# 04_-_ZYNQ_POWER_AND_JTAG.net
KiCad netlist of a schematic drawn in Altium Designer
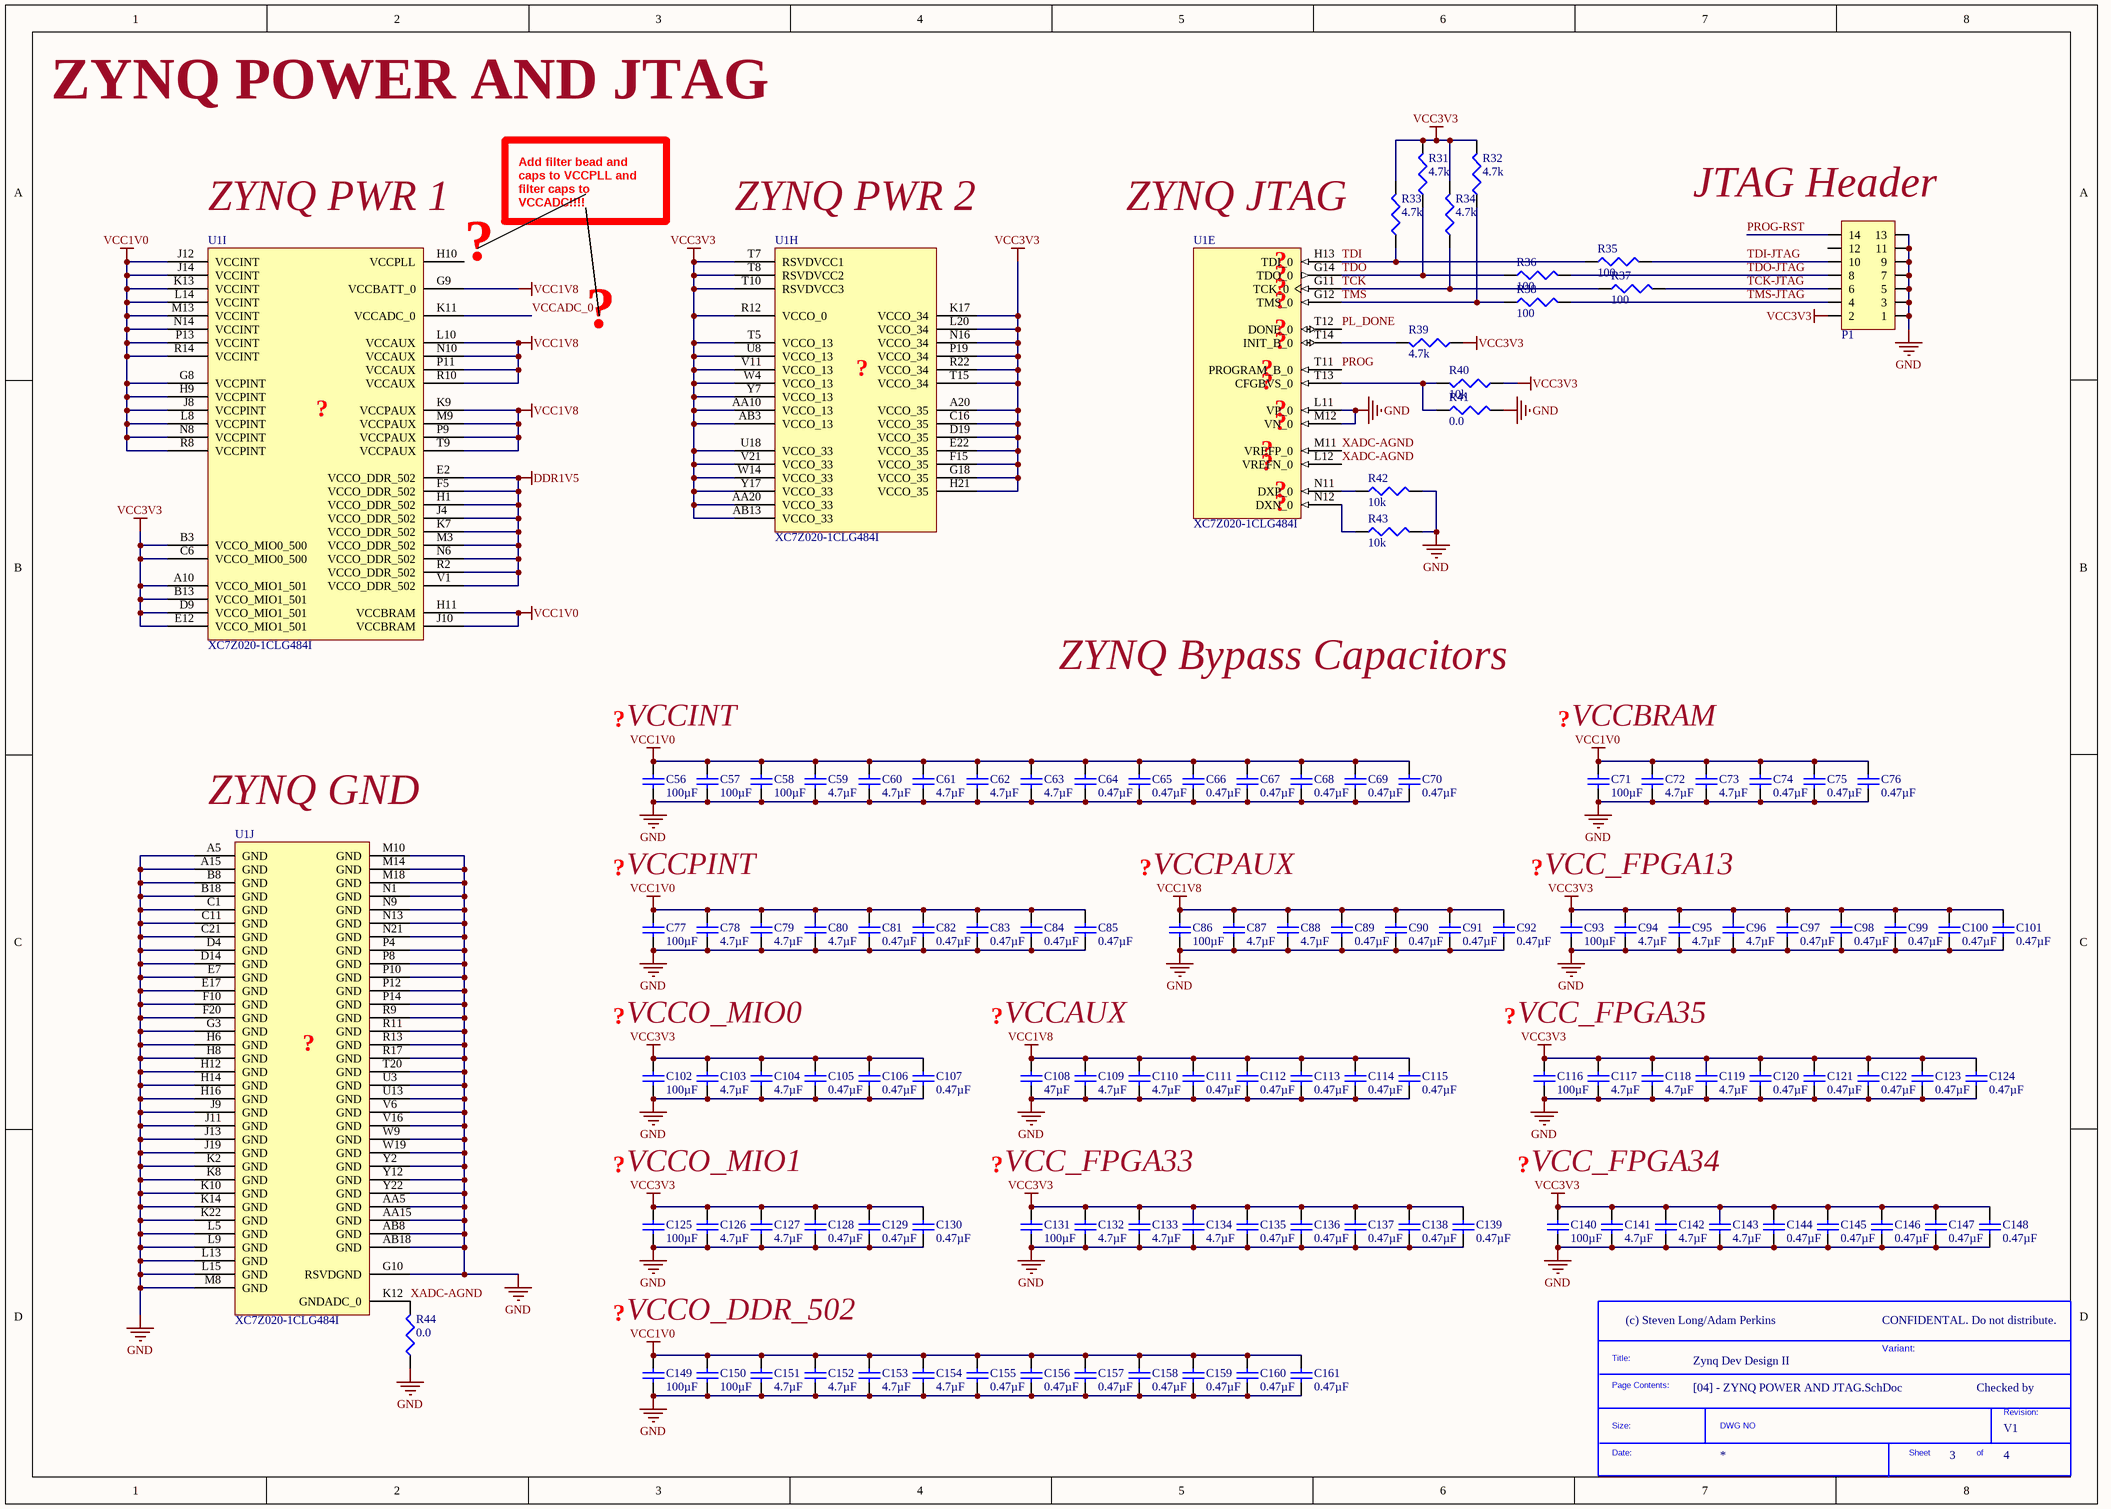
[diagram p0: [04] - ZYNQ POWER AND JTAG.SchDoc]

(export (version "E")
  (design (tool "Eeschema 10.0.6"))
  (components
    (comp (ref "C56")
      (value "GRM32EE70G107ME19L")
      (footprint "CAP-1210")
      (description "CAP CER 100UF 4V X7U 1210")
      (fields
        (field (name "MANUFACTURER") "Murata Electronics North America")
        (field (name "TOLERANCE") "±20%")
        (field (name "CAPACITANCE") "100µF")
      )
      (libsource (lib "zynq_dev_V1") (part "GRM32EE70G107ME19L"))
    )
    (comp (ref "C57")
      (value "GRM32EE70G107ME19L")
      (footprint "CAP-1210")
      (description "CAP CER 100UF 4V X7U 1210")
      (fields
        (field (name "MANUFACTURER") "Murata Electronics North America")
        (field (name "TOLERANCE") "±20%")
        (field (name "CAPACITANCE") "100µF")
      )
      (libsource (lib "zynq_dev_V1") (part "GRM32EE70G107ME19L"))
    )
    (comp (ref "C58")
      (value "GRM32EE70G107ME19L")
      (footprint "CAP-1210")
      (description "CAP CER 100UF 4V X7U 1210")
      (fields
        (field (name "MANUFACTURER") "Murata Electronics North America")
        (field (name "TOLERANCE") "±20%")
        (field (name "CAPACITANCE") "100µF")
      )
      (libsource (lib "zynq_dev_V1") (part "GRM32EE70G107ME19L"))
    )
    (comp (ref "C59")
      (value "GRM188R60J475KE19D")
      (footprint "CAP-0603")
      (description "CAP CER 4.7UF 6.3V X5R 0603")
      (fields
        (field (name "MANUFACTURER") "Murata Electronics North America")
        (field (name "TOLERANCE") "±10%")
        (field (name "CAPACITANCE") "4.7µF")
      )
      (libsource (lib "zynq_dev_V1") (part "GRM188R60J475KE19D"))
    )
    (comp (ref "C60")
      (value "GRM188R60J475KE19D")
      (footprint "CAP-0603")
      (description "CAP CER 4.7UF 6.3V X5R 0603")
      (fields
        (field (name "MANUFACTURER") "Murata Electronics North America")
        (field (name "TOLERANCE") "±10%")
        (field (name "CAPACITANCE") "4.7µF")
      )
      (libsource (lib "zynq_dev_V1") (part "GRM188R60J475KE19D"))
    )
    (comp (ref "C61")
      (value "GRM188R60J475KE19D")
      (footprint "CAP-0603")
      (description "CAP CER 4.7UF 6.3V X5R 0603")
      (fields
        (field (name "MANUFACTURER") "Murata Electronics North America")
        (field (name "TOLERANCE") "±10%")
        (field (name "CAPACITANCE") "4.7µF")
      )
      (libsource (lib "zynq_dev_V1") (part "GRM188R60J475KE19D"))
    )
    (comp (ref "C62")
      (value "GRM188R60J475KE19D")
      (footprint "CAP-0603")
      (description "CAP CER 4.7UF 6.3V X5R 0603")
      (fields
        (field (name "MANUFACTURER") "Murata Electronics North America")
        (field (name "TOLERANCE") "±10%")
        (field (name "CAPACITANCE") "4.7µF")
      )
      (libsource (lib "zynq_dev_V1") (part "GRM188R60J475KE19D"))
    )
    (comp (ref "C63")
      (value "GRM188R60J475KE19D")
      (footprint "CAP-0603")
      (description "CAP CER 4.7UF 6.3V X5R 0603")
      (fields
        (field (name "MANUFACTURER") "Murata Electronics North America")
        (field (name "TOLERANCE") "±10%")
        (field (name "CAPACITANCE") "4.7µF")
      )
      (libsource (lib "zynq_dev_V1") (part "GRM188R60J475KE19D"))
    )
    (comp (ref "C64")
      (value "C1005X7S1A474K050BC")
      (footprint "CAP-0402")
      (description "CAP CER 0.47UF 10V X7S 0402")
      (fields
        (field (name "MANUFACTURER") "TDK Corporation")
        (field (name "TOLERANCE") "±10%")
        (field (name "CAPACITANCE") "0.47µF")
      )
      (libsource (lib "zynq_dev_V1") (part "C1005X7S1A474K050BC"))
    )
    (comp (ref "C65")
      (value "C1005X7S1A474K050BC")
      (footprint "CAP-0402")
      (description "CAP CER 0.47UF 10V X7S 0402")
      (fields
        (field (name "MANUFACTURER") "TDK Corporation")
        (field (name "TOLERANCE") "±10%")
        (field (name "CAPACITANCE") "0.47µF")
      )
      (libsource (lib "zynq_dev_V1") (part "C1005X7S1A474K050BC"))
    )
    (comp (ref "C66")
      (value "C1005X7S1A474K050BC")
      (footprint "CAP-0402")
      (description "CAP CER 0.47UF 10V X7S 0402")
      (fields
        (field (name "MANUFACTURER") "TDK Corporation")
        (field (name "TOLERANCE") "±10%")
        (field (name "CAPACITANCE") "0.47µF")
      )
      (libsource (lib "zynq_dev_V1") (part "C1005X7S1A474K050BC"))
    )
    (comp (ref "C67")
      (value "C1005X7S1A474K050BC")
      (footprint "CAP-0402")
      (description "CAP CER 0.47UF 10V X7S 0402")
      (fields
        (field (name "MANUFACTURER") "TDK Corporation")
        (field (name "TOLERANCE") "±10%")
        (field (name "CAPACITANCE") "0.47µF")
      )
      (libsource (lib "zynq_dev_V1") (part "C1005X7S1A474K050BC"))
    )
    (comp (ref "C68")
      (value "C1005X7S1A474K050BC")
      (footprint "CAP-0402")
      (description "CAP CER 0.47UF 10V X7S 0402")
      (fields
        (field (name "MANUFACTURER") "TDK Corporation")
        (field (name "TOLERANCE") "±10%")
        (field (name "CAPACITANCE") "0.47µF")
      )
      (libsource (lib "zynq_dev_V1") (part "C1005X7S1A474K050BC"))
    )
    (comp (ref "C69")
      (value "C1005X7S1A474K050BC")
      (footprint "CAP-0402")
      (description "CAP CER 0.47UF 10V X7S 0402")
      (fields
        (field (name "MANUFACTURER") "TDK Corporation")
        (field (name "TOLERANCE") "±10%")
        (field (name "CAPACITANCE") "0.47µF")
      )
      (libsource (lib "zynq_dev_V1") (part "C1005X7S1A474K050BC"))
    )
    (comp (ref "C70")
      (value "C1005X7S1A474K050BC")
      (footprint "CAP-0402")
      (description "CAP CER 0.47UF 10V X7S 0402")
      (fields
        (field (name "MANUFACTURER") "TDK Corporation")
        (field (name "TOLERANCE") "±10%")
        (field (name "CAPACITANCE") "0.47µF")
      )
      (libsource (lib "zynq_dev_V1") (part "C1005X7S1A474K050BC"))
    )
    (comp (ref "C71")
      (value "GRM32EE70G107ME19L")
      (footprint "CAP-1210")
      (description "CAP CER 100UF 4V X7U 1210")
      (fields
        (field (name "MANUFACTURER") "Murata Electronics North America")
        (field (name "TOLERANCE") "±20%")
        (field (name "CAPACITANCE") "100µF")
      )
      (libsource (lib "zynq_dev_V1") (part "GRM32EE70G107ME19L"))
    )
    (comp (ref "C72")
      (value "GRM188R60J475KE19D")
      (footprint "CAP-0603")
      (description "CAP CER 4.7UF 6.3V X5R 0603")
      (fields
        (field (name "MANUFACTURER") "Murata Electronics North America")
        (field (name "TOLERANCE") "±10%")
        (field (name "CAPACITANCE") "4.7µF")
      )
      (libsource (lib "zynq_dev_V1") (part "GRM188R60J475KE19D"))
    )
    (comp (ref "C73")
      (value "GRM188R60J475KE19D")
      (footprint "CAP-0603")
      (description "CAP CER 4.7UF 6.3V X5R 0603")
      (fields
        (field (name "MANUFACTURER") "Murata Electronics North America")
        (field (name "TOLERANCE") "±10%")
        (field (name "CAPACITANCE") "4.7µF")
      )
      (libsource (lib "zynq_dev_V1") (part "GRM188R60J475KE19D"))
    )
    (comp (ref "C74")
      (value "C1005X7S1A474K050BC")
      (footprint "CAP-0402")
      (description "CAP CER 0.47UF 10V X7S 0402")
      (fields
        (field (name "MANUFACTURER") "TDK Corporation")
        (field (name "TOLERANCE") "±10%")
        (field (name "CAPACITANCE") "0.47µF")
      )
      (libsource (lib "zynq_dev_V1") (part "C1005X7S1A474K050BC"))
    )
    (comp (ref "C75")
      (value "C1005X7S1A474K050BC")
      (footprint "CAP-0402")
      (description "CAP CER 0.47UF 10V X7S 0402")
      (fields
        (field (name "MANUFACTURER") "TDK Corporation")
        (field (name "TOLERANCE") "±10%")
        (field (name "CAPACITANCE") "0.47µF")
      )
      (libsource (lib "zynq_dev_V1") (part "C1005X7S1A474K050BC"))
    )
    (comp (ref "C76")
      (value "C1005X7S1A474K050BC")
      (footprint "CAP-0402")
      (description "CAP CER 0.47UF 10V X7S 0402")
      (fields
        (field (name "MANUFACTURER") "TDK Corporation")
        (field (name "TOLERANCE") "±10%")
        (field (name "CAPACITANCE") "0.47µF")
      )
      (libsource (lib "zynq_dev_V1") (part "C1005X7S1A474K050BC"))
    )
    (comp (ref "C77")
      (value "GRM32EE70G107ME19L")
      (footprint "CAP-1210")
      (description "CAP CER 100UF 4V X7U 1210")
      (fields
        (field (name "MANUFACTURER") "Murata Electronics North America")
        (field (name "TOLERANCE") "±20%")
        (field (name "CAPACITANCE") "100µF")
      )
      (libsource (lib "zynq_dev_V1") (part "GRM32EE70G107ME19L"))
    )
    (comp (ref "C78")
      (value "GRM188R60J475KE19D")
      (footprint "CAP-0603")
      (description "CAP CER 4.7UF 6.3V X5R 0603")
      (fields
        (field (name "MANUFACTURER") "Murata Electronics North America")
        (field (name "TOLERANCE") "±10%")
        (field (name "CAPACITANCE") "4.7µF")
      )
      (libsource (lib "zynq_dev_V1") (part "GRM188R60J475KE19D"))
    )
    (comp (ref "C79")
      (value "GRM188R60J475KE19D")
      (footprint "CAP-0603")
      (description "CAP CER 4.7UF 6.3V X5R 0603")
      (fields
        (field (name "MANUFACTURER") "Murata Electronics North America")
        (field (name "TOLERANCE") "±10%")
        (field (name "CAPACITANCE") "4.7µF")
      )
      (libsource (lib "zynq_dev_V1") (part "GRM188R60J475KE19D"))
    )
    (comp (ref "C80")
      (value "GRM188R60J475KE19D")
      (footprint "CAP-0603")
      (description "CAP CER 4.7UF 6.3V X5R 0603")
      (fields
        (field (name "MANUFACTURER") "Murata Electronics North America")
        (field (name "TOLERANCE") "±10%")
        (field (name "CAPACITANCE") "4.7µF")
      )
      (libsource (lib "zynq_dev_V1") (part "GRM188R60J475KE19D"))
    )
    (comp (ref "C81")
      (value "C1005X7S1A474K050BC")
      (footprint "CAP-0402")
      (description "CAP CER 0.47UF 10V X7S 0402")
      (fields
        (field (name "MANUFACTURER") "TDK Corporation")
        (field (name "TOLERANCE") "±10%")
        (field (name "CAPACITANCE") "0.47µF")
      )
      (libsource (lib "zynq_dev_V1") (part "C1005X7S1A474K050BC"))
    )
    (comp (ref "C82")
      (value "C1005X7S1A474K050BC")
      (footprint "CAP-0402")
      (description "CAP CER 0.47UF 10V X7S 0402")
      (fields
        (field (name "MANUFACTURER") "TDK Corporation")
        (field (name "TOLERANCE") "±10%")
        (field (name "CAPACITANCE") "0.47µF")
      )
      (libsource (lib "zynq_dev_V1") (part "C1005X7S1A474K050BC"))
    )
    (comp (ref "C83")
      (value "C1005X7S1A474K050BC")
      (footprint "CAP-0402")
      (description "CAP CER 0.47UF 10V X7S 0402")
      (fields
        (field (name "MANUFACTURER") "TDK Corporation")
        (field (name "TOLERANCE") "±10%")
        (field (name "CAPACITANCE") "0.47µF")
      )
      (libsource (lib "zynq_dev_V1") (part "C1005X7S1A474K050BC"))
    )
    (comp (ref "C84")
      (value "C1005X7S1A474K050BC")
      (footprint "CAP-0402")
      (description "CAP CER 0.47UF 10V X7S 0402")
      (fields
        (field (name "MANUFACTURER") "TDK Corporation")
        (field (name "TOLERANCE") "±10%")
        (field (name "CAPACITANCE") "0.47µF")
      )
      (libsource (lib "zynq_dev_V1") (part "C1005X7S1A474K050BC"))
    )
    (comp (ref "C85")
      (value "C1005X7S1A474K050BC")
      (footprint "CAP-0402")
      (description "CAP CER 0.47UF 10V X7S 0402")
      (fields
        (field (name "MANUFACTURER") "TDK Corporation")
        (field (name "TOLERANCE") "±10%")
        (field (name "CAPACITANCE") "0.47µF")
      )
      (libsource (lib "zynq_dev_V1") (part "C1005X7S1A474K050BC"))
    )
    (comp (ref "C86")
      (value "GRM32EE70G107ME19L")
      (footprint "CAP-1210")
      (description "CAP CER 100UF 4V X7U 1210")
      (fields
        (field (name "MANUFACTURER") "Murata Electronics North America")
        (field (name "TOLERANCE") "±20%")
        (field (name "CAPACITANCE") "100µF")
      )
      (libsource (lib "zynq_dev_V1") (part "GRM32EE70G107ME19L"))
    )
    (comp (ref "C87")
      (value "GRM188R60J475KE19D")
      (footprint "CAP-0603")
      (description "CAP CER 4.7UF 6.3V X5R 0603")
      (fields
        (field (name "MANUFACTURER") "Murata Electronics North America")
        (field (name "TOLERANCE") "±10%")
        (field (name "CAPACITANCE") "4.7µF")
      )
      (libsource (lib "zynq_dev_V1") (part "GRM188R60J475KE19D"))
    )
    (comp (ref "C88")
      (value "GRM188R60J475KE19D")
      (footprint "CAP-0603")
      (description "CAP CER 4.7UF 6.3V X5R 0603")
      (fields
        (field (name "MANUFACTURER") "Murata Electronics North America")
        (field (name "TOLERANCE") "±10%")
        (field (name "CAPACITANCE") "4.7µF")
      )
      (libsource (lib "zynq_dev_V1") (part "GRM188R60J475KE19D"))
    )
    (comp (ref "C89")
      (value "C1005X7S1A474K050BC")
      (footprint "CAP-0402")
      (description "CAP CER 0.47UF 10V X7S 0402")
      (fields
        (field (name "MANUFACTURER") "TDK Corporation")
        (field (name "TOLERANCE") "±10%")
        (field (name "CAPACITANCE") "0.47µF")
      )
      (libsource (lib "zynq_dev_V1") (part "C1005X7S1A474K050BC"))
    )
    (comp (ref "C90")
      (value "C1005X7S1A474K050BC")
      (footprint "CAP-0402")
      (description "CAP CER 0.47UF 10V X7S 0402")
      (fields
        (field (name "MANUFACTURER") "TDK Corporation")
        (field (name "TOLERANCE") "±10%")
        (field (name "CAPACITANCE") "0.47µF")
      )
      (libsource (lib "zynq_dev_V1") (part "C1005X7S1A474K050BC"))
    )
    (comp (ref "C91")
      (value "C1005X7S1A474K050BC")
      (footprint "CAP-0402")
      (description "CAP CER 0.47UF 10V X7S 0402")
      (fields
        (field (name "MANUFACTURER") "TDK Corporation")
        (field (name "TOLERANCE") "±10%")
        (field (name "CAPACITANCE") "0.47µF")
      )
      (libsource (lib "zynq_dev_V1") (part "C1005X7S1A474K050BC"))
    )
    (comp (ref "C92")
      (value "C1005X7S1A474K050BC")
      (footprint "CAP-0402")
      (description "CAP CER 0.47UF 10V X7S 0402")
      (fields
        (field (name "MANUFACTURER") "TDK Corporation")
        (field (name "TOLERANCE") "±10%")
        (field (name "CAPACITANCE") "0.47µF")
      )
      (libsource (lib "zynq_dev_V1") (part "C1005X7S1A474K050BC"))
    )
    (comp (ref "C93")
      (value "GRM32EE70G107ME19L")
      (footprint "CAP-1210")
      (description "CAP CER 100UF 4V X7U 1210")
      (fields
        (field (name "MANUFACTURER") "Murata Electronics North America")
        (field (name "TOLERANCE") "±20%")
        (field (name "CAPACITANCE") "100µF")
      )
      (libsource (lib "zynq_dev_V1") (part "GRM32EE70G107ME19L"))
    )
    (comp (ref "C94")
      (value "GRM188R60J475KE19D")
      (footprint "CAP-0603")
      (description "CAP CER 4.7UF 6.3V X5R 0603")
      (fields
        (field (name "MANUFACTURER") "Murata Electronics North America")
        (field (name "TOLERANCE") "±10%")
        (field (name "CAPACITANCE") "4.7µF")
      )
      (libsource (lib "zynq_dev_V1") (part "GRM188R60J475KE19D"))
    )
    (comp (ref "C95")
      (value "GRM188R60J475KE19D")
      (footprint "CAP-0603")
      (description "CAP CER 4.7UF 6.3V X5R 0603")
      (fields
        (field (name "MANUFACTURER") "Murata Electronics North America")
        (field (name "TOLERANCE") "±10%")
        (field (name "CAPACITANCE") "4.7µF")
      )
      (libsource (lib "zynq_dev_V1") (part "GRM188R60J475KE19D"))
    )
    (comp (ref "C96")
      (value "GRM188R60J475KE19D")
      (footprint "CAP-0603")
      (description "CAP CER 4.7UF 6.3V X5R 0603")
      (fields
        (field (name "MANUFACTURER") "Murata Electronics North America")
        (field (name "TOLERANCE") "±10%")
        (field (name "CAPACITANCE") "4.7µF")
      )
      (libsource (lib "zynq_dev_V1") (part "GRM188R60J475KE19D"))
    )
    (comp (ref "C97")
      (value "C1005X7S1A474K050BC")
      (footprint "CAP-0402")
      (description "CAP CER 0.47UF 10V X7S 0402")
      (fields
        (field (name "MANUFACTURER") "TDK Corporation")
        (field (name "TOLERANCE") "±10%")
        (field (name "CAPACITANCE") "0.47µF")
      )
      (libsource (lib "zynq_dev_V1") (part "C1005X7S1A474K050BC"))
    )
    (comp (ref "C98")
      (value "C1005X7S1A474K050BC")
      (footprint "CAP-0402")
      (description "CAP CER 0.47UF 10V X7S 0402")
      (fields
        (field (name "MANUFACTURER") "TDK Corporation")
        (field (name "TOLERANCE") "±10%")
        (field (name "CAPACITANCE") "0.47µF")
      )
      (libsource (lib "zynq_dev_V1") (part "C1005X7S1A474K050BC"))
    )
    (comp (ref "C99")
      (value "C1005X7S1A474K050BC")
      (footprint "CAP-0402")
      (description "CAP CER 0.47UF 10V X7S 0402")
      (fields
        (field (name "MANUFACTURER") "TDK Corporation")
        (field (name "TOLERANCE") "±10%")
        (field (name "CAPACITANCE") "0.47µF")
      )
      (libsource (lib "zynq_dev_V1") (part "C1005X7S1A474K050BC"))
    )
    (comp (ref "C100")
      (value "C1005X7S1A474K050BC")
      (footprint "CAP-0402")
      (description "CAP CER 0.47UF 10V X7S 0402")
      (fields
        (field (name "MANUFACTURER") "TDK Corporation")
        (field (name "TOLERANCE") "±10%")
        (field (name "CAPACITANCE") "0.47µF")
      )
      (libsource (lib "zynq_dev_V1") (part "C1005X7S1A474K050BC"))
    )
    (comp (ref "C101")
      (value "C1005X7S1A474K050BC")
      (footprint "CAP-0402")
      (description "CAP CER 0.47UF 10V X7S 0402")
      (fields
        (field (name "MANUFACTURER") "TDK Corporation")
        (field (name "TOLERANCE") "±10%")
        (field (name "CAPACITANCE") "0.47µF")
      )
      (libsource (lib "zynq_dev_V1") (part "C1005X7S1A474K050BC"))
    )
    (comp (ref "C102")
      (value "GRM32EE70G107ME19L")
      (footprint "CAP-1210")
      (description "CAP CER 100UF 4V X7U 1210")
      (fields
        (field (name "MANUFACTURER") "Murata Electronics North America")
        (field (name "TOLERANCE") "±20%")
        (field (name "CAPACITANCE") "100µF")
      )
      (libsource (lib "zynq_dev_V1") (part "GRM32EE70G107ME19L"))
    )
    (comp (ref "C103")
      (value "GRM188R60J475KE19D")
      (footprint "CAP-0603")
      (description "CAP CER 4.7UF 6.3V X5R 0603")
      (fields
        (field (name "MANUFACTURER") "Murata Electronics North America")
        (field (name "TOLERANCE") "±10%")
        (field (name "CAPACITANCE") "4.7µF")
      )
      (libsource (lib "zynq_dev_V1") (part "GRM188R60J475KE19D"))
    )
    (comp (ref "C104")
      (value "GRM188R60J475KE19D")
      (footprint "CAP-0603")
      (description "CAP CER 4.7UF 6.3V X5R 0603")
      (fields
        (field (name "MANUFACTURER") "Murata Electronics North America")
        (field (name "TOLERANCE") "±10%")
        (field (name "CAPACITANCE") "4.7µF")
      )
      (libsource (lib "zynq_dev_V1") (part "GRM188R60J475KE19D"))
    )
    (comp (ref "C105")
      (value "C1005X7S1A474K050BC")
      (footprint "CAP-0402")
      (description "CAP CER 0.47UF 10V X7S 0402")
      (fields
        (field (name "MANUFACTURER") "TDK Corporation")
        (field (name "TOLERANCE") "±10%")
        (field (name "CAPACITANCE") "0.47µF")
      )
      (libsource (lib "zynq_dev_V1") (part "C1005X7S1A474K050BC"))
    )
    (comp (ref "C106")
      (value "C1005X7S1A474K050BC")
      (footprint "CAP-0402")
      (description "CAP CER 0.47UF 10V X7S 0402")
      (fields
        (field (name "MANUFACTURER") "TDK Corporation")
        (field (name "TOLERANCE") "±10%")
        (field (name "CAPACITANCE") "0.47µF")
      )
      (libsource (lib "zynq_dev_V1") (part "C1005X7S1A474K050BC"))
    )
    (comp (ref "C107")
      (value "C1005X7S1A474K050BC")
      (footprint "CAP-0402")
      (description "CAP CER 0.47UF 10V X7S 0402")
      (fields
        (field (name "MANUFACTURER") "TDK Corporation")
        (field (name "TOLERANCE") "±10%")
        (field (name "CAPACITANCE") "0.47µF")
      )
      (libsource (lib "zynq_dev_V1") (part "C1005X7S1A474K050BC"))
    )
    (comp (ref "C108")
      (value "GRM32ER61C476ME15L")
      (footprint "CAP-1210")
      (description "CAP CER 47UF 16V X5R 1210")
      (fields
        (field (name "MANUFACTURER") "Murata Electronics North America")
        (field (name "TOLERANCE") "±20%")
        (field (name "CAPACITANCE") "47µF")
      )
      (libsource (lib "zynq_dev_V1") (part "GRM32ER61C476ME15L"))
    )
    (comp (ref "C109")
      (value "GRM188R60J475KE19D")
      (footprint "CAP-0603")
      (description "CAP CER 4.7UF 6.3V X5R 0603")
      (fields
        (field (name "MANUFACTURER") "Murata Electronics North America")
        (field (name "TOLERANCE") "±10%")
        (field (name "CAPACITANCE") "4.7µF")
      )
      (libsource (lib "zynq_dev_V1") (part "GRM188R60J475KE19D"))
    )
    (comp (ref "C110")
      (value "GRM188R60J475KE19D")
      (footprint "CAP-0603")
      (description "CAP CER 4.7UF 6.3V X5R 0603")
      (fields
        (field (name "MANUFACTURER") "Murata Electronics North America")
        (field (name "TOLERANCE") "±10%")
        (field (name "CAPACITANCE") "4.7µF")
      )
      (libsource (lib "zynq_dev_V1") (part "GRM188R60J475KE19D"))
    )
    (comp (ref "C111")
      (value "C1005X7S1A474K050BC")
      (footprint "CAP-0402")
      (description "CAP CER 0.47UF 10V X7S 0402")
      (fields
        (field (name "MANUFACTURER") "TDK Corporation")
        (field (name "TOLERANCE") "±10%")
        (field (name "CAPACITANCE") "0.47µF")
      )
      (libsource (lib "zynq_dev_V1") (part "C1005X7S1A474K050BC"))
    )
    (comp (ref "C112")
      (value "C1005X7S1A474K050BC")
      (footprint "CAP-0402")
      (description "CAP CER 0.47UF 10V X7S 0402")
      (fields
        (field (name "MANUFACTURER") "TDK Corporation")
        (field (name "TOLERANCE") "±10%")
        (field (name "CAPACITANCE") "0.47µF")
      )
      (libsource (lib "zynq_dev_V1") (part "C1005X7S1A474K050BC"))
    )
    (comp (ref "C113")
      (value "C1005X7S1A474K050BC")
      (footprint "CAP-0402")
      (description "CAP CER 0.47UF 10V X7S 0402")
      (fields
        (field (name "MANUFACTURER") "TDK Corporation")
        (field (name "TOLERANCE") "±10%")
        (field (name "CAPACITANCE") "0.47µF")
      )
      (libsource (lib "zynq_dev_V1") (part "C1005X7S1A474K050BC"))
    )
    (comp (ref "C114")
      (value "C1005X7S1A474K050BC")
      (footprint "CAP-0402")
      (description "CAP CER 0.47UF 10V X7S 0402")
      (fields
        (field (name "MANUFACTURER") "TDK Corporation")
        (field (name "TOLERANCE") "±10%")
        (field (name "CAPACITANCE") "0.47µF")
      )
      (libsource (lib "zynq_dev_V1") (part "C1005X7S1A474K050BC"))
    )
    (comp (ref "C115")
      (value "C1005X7S1A474K050BC")
      (footprint "CAP-0402")
      (description "CAP CER 0.47UF 10V X7S 0402")
      (fields
        (field (name "MANUFACTURER") "TDK Corporation")
        (field (name "TOLERANCE") "±10%")
        (field (name "CAPACITANCE") "0.47µF")
      )
      (libsource (lib "zynq_dev_V1") (part "C1005X7S1A474K050BC"))
    )
    (comp (ref "C116")
      (value "GRM32EE70G107ME19L")
      (footprint "CAP-1210")
      (description "CAP CER 100UF 4V X7U 1210")
      (fields
        (field (name "MANUFACTURER") "Murata Electronics North America")
        (field (name "TOLERANCE") "±20%")
        (field (name "CAPACITANCE") "100µF")
      )
      (libsource (lib "zynq_dev_V1") (part "GRM32EE70G107ME19L"))
    )
    (comp (ref "C117")
      (value "GRM188R60J475KE19D")
      (footprint "CAP-0603")
      (description "CAP CER 4.7UF 6.3V X5R 0603")
      (fields
        (field (name "MANUFACTURER") "Murata Electronics North America")
        (field (name "TOLERANCE") "±10%")
        (field (name "CAPACITANCE") "4.7µF")
      )
      (libsource (lib "zynq_dev_V1") (part "GRM188R60J475KE19D"))
    )
    (comp (ref "C118")
      (value "GRM188R60J475KE19D")
      (footprint "CAP-0603")
      (description "CAP CER 4.7UF 6.3V X5R 0603")
      (fields
        (field (name "MANUFACTURER") "Murata Electronics North America")
        (field (name "TOLERANCE") "±10%")
        (field (name "CAPACITANCE") "4.7µF")
      )
      (libsource (lib "zynq_dev_V1") (part "GRM188R60J475KE19D"))
    )
    (comp (ref "C119")
      (value "GRM188R60J475KE19D")
      (footprint "CAP-0603")
      (description "CAP CER 4.7UF 6.3V X5R 0603")
      (fields
        (field (name "MANUFACTURER") "Murata Electronics North America")
        (field (name "TOLERANCE") "±10%")
        (field (name "CAPACITANCE") "4.7µF")
      )
      (libsource (lib "zynq_dev_V1") (part "GRM188R60J475KE19D"))
    )
    (comp (ref "C120")
      (value "C1005X7S1A474K050BC")
      (footprint "CAP-0402")
      (description "CAP CER 0.47UF 10V X7S 0402")
      (fields
        (field (name "MANUFACTURER") "TDK Corporation")
        (field (name "TOLERANCE") "±10%")
        (field (name "CAPACITANCE") "0.47µF")
      )
      (libsource (lib "zynq_dev_V1") (part "C1005X7S1A474K050BC"))
    )
    (comp (ref "C121")
      (value "C1005X7S1A474K050BC")
      (footprint "CAP-0402")
      (description "CAP CER 0.47UF 10V X7S 0402")
      (fields
        (field (name "MANUFACTURER") "TDK Corporation")
        (field (name "TOLERANCE") "±10%")
        (field (name "CAPACITANCE") "0.47µF")
      )
      (libsource (lib "zynq_dev_V1") (part "C1005X7S1A474K050BC"))
    )
    (comp (ref "C122")
      (value "C1005X7S1A474K050BC")
      (footprint "CAP-0402")
      (description "CAP CER 0.47UF 10V X7S 0402")
      (fields
        (field (name "MANUFACTURER") "TDK Corporation")
        (field (name "TOLERANCE") "±10%")
        (field (name "CAPACITANCE") "0.47µF")
      )
      (libsource (lib "zynq_dev_V1") (part "C1005X7S1A474K050BC"))
    )
    (comp (ref "C123")
      (value "C1005X7S1A474K050BC")
      (footprint "CAP-0402")
      (description "CAP CER 0.47UF 10V X7S 0402")
      (fields
        (field (name "MANUFACTURER") "TDK Corporation")
        (field (name "TOLERANCE") "±10%")
        (field (name "CAPACITANCE") "0.47µF")
      )
      (libsource (lib "zynq_dev_V1") (part "C1005X7S1A474K050BC"))
    )
    (comp (ref "C124")
      (value "C1005X7S1A474K050BC")
      (footprint "CAP-0402")
      (description "CAP CER 0.47UF 10V X7S 0402")
      (fields
        (field (name "MANUFACTURER") "TDK Corporation")
        (field (name "TOLERANCE") "±10%")
        (field (name "CAPACITANCE") "0.47µF")
      )
      (libsource (lib "zynq_dev_V1") (part "C1005X7S1A474K050BC"))
    )
    (comp (ref "C125")
      (value "GRM32EE70G107ME19L")
      (footprint "CAP-1210")
      (description "CAP CER 100UF 4V X7U 1210")
      (fields
        (field (name "MANUFACTURER") "Murata Electronics North America")
        (field (name "TOLERANCE") "±20%")
        (field (name "CAPACITANCE") "100µF")
      )
      (libsource (lib "zynq_dev_V1") (part "GRM32EE70G107ME19L"))
    )
    (comp (ref "C126")
      (value "GRM188R60J475KE19D")
      (footprint "CAP-0603")
      (description "CAP CER 4.7UF 6.3V X5R 0603")
      (fields
        (field (name "MANUFACTURER") "Murata Electronics North America")
        (field (name "TOLERANCE") "±10%")
        (field (name "CAPACITANCE") "4.7µF")
      )
      (libsource (lib "zynq_dev_V1") (part "GRM188R60J475KE19D"))
    )
    (comp (ref "C127")
      (value "GRM188R60J475KE19D")
      (footprint "CAP-0603")
      (description "CAP CER 4.7UF 6.3V X5R 0603")
      (fields
        (field (name "MANUFACTURER") "Murata Electronics North America")
        (field (name "TOLERANCE") "±10%")
        (field (name "CAPACITANCE") "4.7µF")
      )
      (libsource (lib "zynq_dev_V1") (part "GRM188R60J475KE19D"))
    )
    (comp (ref "C128")
      (value "C1005X7S1A474K050BC")
      (footprint "CAP-0402")
      (description "CAP CER 0.47UF 10V X7S 0402")
      (fields
        (field (name "MANUFACTURER") "TDK Corporation")
        (field (name "TOLERANCE") "±10%")
        (field (name "CAPACITANCE") "0.47µF")
      )
      (libsource (lib "zynq_dev_V1") (part "C1005X7S1A474K050BC"))
    )
    (comp (ref "C129")
      (value "C1005X7S1A474K050BC")
      (footprint "CAP-0402")
      (description "CAP CER 0.47UF 10V X7S 0402")
      (fields
        (field (name "MANUFACTURER") "TDK Corporation")
        (field (name "TOLERANCE") "±10%")
        (field (name "CAPACITANCE") "0.47µF")
      )
      (libsource (lib "zynq_dev_V1") (part "C1005X7S1A474K050BC"))
    )
    (comp (ref "C130")
      (value "C1005X7S1A474K050BC")
      (footprint "CAP-0402")
      (description "CAP CER 0.47UF 10V X7S 0402")
      (fields
        (field (name "MANUFACTURER") "TDK Corporation")
        (field (name "TOLERANCE") "±10%")
        (field (name "CAPACITANCE") "0.47µF")
      )
      (libsource (lib "zynq_dev_V1") (part "C1005X7S1A474K050BC"))
    )
    (comp (ref "C131")
      (value "GRM32EE70G107ME19L")
      (footprint "CAP-1210")
      (description "CAP CER 100UF 4V X7U 1210")
      (fields
        (field (name "MANUFACTURER") "Murata Electronics North America")
        (field (name "TOLERANCE") "±20%")
        (field (name "CAPACITANCE") "100µF")
      )
      (libsource (lib "zynq_dev_V1") (part "GRM32EE70G107ME19L"))
    )
    (comp (ref "C132")
      (value "GRM188R60J475KE19D")
      (footprint "CAP-0603")
      (description "CAP CER 4.7UF 6.3V X5R 0603")
      (fields
        (field (name "MANUFACTURER") "Murata Electronics North America")
        (field (name "TOLERANCE") "±10%")
        (field (name "CAPACITANCE") "4.7µF")
      )
      (libsource (lib "zynq_dev_V1") (part "GRM188R60J475KE19D"))
    )
    (comp (ref "C133")
      (value "GRM188R60J475KE19D")
      (footprint "CAP-0603")
      (description "CAP CER 4.7UF 6.3V X5R 0603")
      (fields
        (field (name "MANUFACTURER") "Murata Electronics North America")
        (field (name "TOLERANCE") "±10%")
        (field (name "CAPACITANCE") "4.7µF")
      )
      (libsource (lib "zynq_dev_V1") (part "GRM188R60J475KE19D"))
    )
    (comp (ref "C134")
      (value "GRM188R60J475KE19D")
      (footprint "CAP-0603")
      (description "CAP CER 4.7UF 6.3V X5R 0603")
      (fields
        (field (name "MANUFACTURER") "Murata Electronics North America")
        (field (name "TOLERANCE") "±10%")
        (field (name "CAPACITANCE") "4.7µF")
      )
      (libsource (lib "zynq_dev_V1") (part "GRM188R60J475KE19D"))
    )
    (comp (ref "C135")
      (value "C1005X7S1A474K050BC")
      (footprint "CAP-0402")
      (description "CAP CER 0.47UF 10V X7S 0402")
      (fields
        (field (name "MANUFACTURER") "TDK Corporation")
        (field (name "TOLERANCE") "±10%")
        (field (name "CAPACITANCE") "0.47µF")
      )
      (libsource (lib "zynq_dev_V1") (part "C1005X7S1A474K050BC"))
    )
    (comp (ref "C136")
      (value "C1005X7S1A474K050BC")
      (footprint "CAP-0402")
      (description "CAP CER 0.47UF 10V X7S 0402")
      (fields
        (field (name "MANUFACTURER") "TDK Corporation")
        (field (name "TOLERANCE") "±10%")
        (field (name "CAPACITANCE") "0.47µF")
      )
      (libsource (lib "zynq_dev_V1") (part "C1005X7S1A474K050BC"))
    )
    (comp (ref "C137")
      (value "C1005X7S1A474K050BC")
      (footprint "CAP-0402")
      (description "CAP CER 0.47UF 10V X7S 0402")
      (fields
        (field (name "MANUFACTURER") "TDK Corporation")
        (field (name "TOLERANCE") "±10%")
        (field (name "CAPACITANCE") "0.47µF")
      )
      (libsource (lib "zynq_dev_V1") (part "C1005X7S1A474K050BC"))
    )
    (comp (ref "C138")
      (value "C1005X7S1A474K050BC")
      (footprint "CAP-0402")
      (description "CAP CER 0.47UF 10V X7S 0402")
      (fields
        (field (name "MANUFACTURER") "TDK Corporation")
        (field (name "TOLERANCE") "±10%")
        (field (name "CAPACITANCE") "0.47µF")
      )
      (libsource (lib "zynq_dev_V1") (part "C1005X7S1A474K050BC"))
    )
    (comp (ref "C139")
      (value "C1005X7S1A474K050BC")
      (footprint "CAP-0402")
      (description "CAP CER 0.47UF 10V X7S 0402")
      (fields
        (field (name "MANUFACTURER") "TDK Corporation")
        (field (name "TOLERANCE") "±10%")
        (field (name "CAPACITANCE") "0.47µF")
      )
      (libsource (lib "zynq_dev_V1") (part "C1005X7S1A474K050BC"))
    )
    (comp (ref "C140")
      (value "GRM32EE70G107ME19L")
      (footprint "CAP-1210")
      (description "CAP CER 100UF 4V X7U 1210")
      (fields
        (field (name "MANUFACTURER") "Murata Electronics North America")
        (field (name "TOLERANCE") "±20%")
        (field (name "CAPACITANCE") "100µF")
      )
      (libsource (lib "zynq_dev_V1") (part "GRM32EE70G107ME19L"))
    )
    (comp (ref "C141")
      (value "GRM188R60J475KE19D")
      (footprint "CAP-0603")
      (description "CAP CER 4.7UF 6.3V X5R 0603")
      (fields
        (field (name "MANUFACTURER") "Murata Electronics North America")
        (field (name "TOLERANCE") "±10%")
        (field (name "CAPACITANCE") "4.7µF")
      )
      (libsource (lib "zynq_dev_V1") (part "GRM188R60J475KE19D"))
    )
    (comp (ref "C142")
      (value "GRM188R60J475KE19D")
      (footprint "CAP-0603")
      (description "CAP CER 4.7UF 6.3V X5R 0603")
      (fields
        (field (name "MANUFACTURER") "Murata Electronics North America")
        (field (name "TOLERANCE") "±10%")
        (field (name "CAPACITANCE") "4.7µF")
      )
      (libsource (lib "zynq_dev_V1") (part "GRM188R60J475KE19D"))
    )
    (comp (ref "C143")
      (value "GRM188R60J475KE19D")
      (footprint "CAP-0603")
      (description "CAP CER 4.7UF 6.3V X5R 0603")
      (fields
        (field (name "MANUFACTURER") "Murata Electronics North America")
        (field (name "TOLERANCE") "±10%")
        (field (name "CAPACITANCE") "4.7µF")
      )
      (libsource (lib "zynq_dev_V1") (part "GRM188R60J475KE19D"))
    )
    (comp (ref "C144")
      (value "C1005X7S1A474K050BC")
      (footprint "CAP-0402")
      (description "CAP CER 0.47UF 10V X7S 0402")
      (fields
        (field (name "MANUFACTURER") "TDK Corporation")
        (field (name "TOLERANCE") "±10%")
        (field (name "CAPACITANCE") "0.47µF")
      )
      (libsource (lib "zynq_dev_V1") (part "C1005X7S1A474K050BC"))
    )
    (comp (ref "C145")
      (value "C1005X7S1A474K050BC")
      (footprint "CAP-0402")
      (description "CAP CER 0.47UF 10V X7S 0402")
      (fields
        (field (name "MANUFACTURER") "TDK Corporation")
        (field (name "TOLERANCE") "±10%")
        (field (name "CAPACITANCE") "0.47µF")
      )
      (libsource (lib "zynq_dev_V1") (part "C1005X7S1A474K050BC"))
    )
    (comp (ref "C146")
      (value "C1005X7S1A474K050BC")
      (footprint "CAP-0402")
      (description "CAP CER 0.47UF 10V X7S 0402")
      (fields
        (field (name "MANUFACTURER") "TDK Corporation")
        (field (name "TOLERANCE") "±10%")
        (field (name "CAPACITANCE") "0.47µF")
      )
      (libsource (lib "zynq_dev_V1") (part "C1005X7S1A474K050BC"))
    )
    (comp (ref "C147")
      (value "C1005X7S1A474K050BC")
      (footprint "CAP-0402")
      (description "CAP CER 0.47UF 10V X7S 0402")
      (fields
        (field (name "MANUFACTURER") "TDK Corporation")
        (field (name "TOLERANCE") "±10%")
        (field (name "CAPACITANCE") "0.47µF")
      )
      (libsource (lib "zynq_dev_V1") (part "C1005X7S1A474K050BC"))
    )
    (comp (ref "C148")
      (value "C1005X7S1A474K050BC")
      (footprint "CAP-0402")
      (description "CAP CER 0.47UF 10V X7S 0402")
      (fields
        (field (name "MANUFACTURER") "TDK Corporation")
        (field (name "TOLERANCE") "±10%")
        (field (name "CAPACITANCE") "0.47µF")
      )
      (libsource (lib "zynq_dev_V1") (part "C1005X7S1A474K050BC"))
    )
    (comp (ref "C149")
      (value "GRM32EE70G107ME19L")
      (footprint "CAP-1210")
      (description "CAP CER 100UF 4V X7U 1210")
      (fields
        (field (name "MANUFACTURER") "Murata Electronics North America")
        (field (name "TOLERANCE") "±20%")
        (field (name "CAPACITANCE") "100µF")
      )
      (libsource (lib "zynq_dev_V1") (part "GRM32EE70G107ME19L"))
    )
    (comp (ref "C150")
      (value "GRM32EE70G107ME19L")
      (footprint "CAP-1210")
      (description "CAP CER 100UF 4V X7U 1210")
      (fields
        (field (name "MANUFACTURER") "Murata Electronics North America")
        (field (name "TOLERANCE") "±20%")
        (field (name "CAPACITANCE") "100µF")
      )
      (libsource (lib "zynq_dev_V1") (part "GRM32EE70G107ME19L"))
    )
    (comp (ref "C151")
      (value "GRM188R60J475KE19D")
      (footprint "CAP-0603")
      (description "CAP CER 4.7UF 6.3V X5R 0603")
      (fields
        (field (name "MANUFACTURER") "Murata Electronics North America")
        (field (name "TOLERANCE") "±10%")
        (field (name "CAPACITANCE") "4.7µF")
      )
      (libsource (lib "zynq_dev_V1") (part "GRM188R60J475KE19D"))
    )
    (comp (ref "C152")
      (value "GRM188R60J475KE19D")
      (footprint "CAP-0603")
      (description "CAP CER 4.7UF 6.3V X5R 0603")
      (fields
        (field (name "MANUFACTURER") "Murata Electronics North America")
        (field (name "TOLERANCE") "±10%")
        (field (name "CAPACITANCE") "4.7µF")
      )
      (libsource (lib "zynq_dev_V1") (part "GRM188R60J475KE19D"))
    )
    (comp (ref "C153")
      (value "GRM188R60J475KE19D")
      (footprint "CAP-0603")
      (description "CAP CER 4.7UF 6.3V X5R 0603")
      (fields
        (field (name "MANUFACTURER") "Murata Electronics North America")
        (field (name "TOLERANCE") "±10%")
        (field (name "CAPACITANCE") "4.7µF")
      )
      (libsource (lib "zynq_dev_V1") (part "GRM188R60J475KE19D"))
    )
    (comp (ref "C154")
      (value "GRM188R60J475KE19D")
      (footprint "CAP-0603")
      (description "CAP CER 4.7UF 6.3V X5R 0603")
      (fields
        (field (name "MANUFACTURER") "Murata Electronics North America")
        (field (name "TOLERANCE") "±10%")
        (field (name "CAPACITANCE") "4.7µF")
      )
      (libsource (lib "zynq_dev_V1") (part "GRM188R60J475KE19D"))
    )
    (comp (ref "C155")
      (value "C1005X7S1A474K050BC")
      (footprint "CAP-0402")
      (description "CAP CER 0.47UF 10V X7S 0402")
      (fields
        (field (name "MANUFACTURER") "TDK Corporation")
        (field (name "TOLERANCE") "±10%")
        (field (name "CAPACITANCE") "0.47µF")
      )
      (libsource (lib "zynq_dev_V1") (part "C1005X7S1A474K050BC"))
    )
    (comp (ref "C156")
      (value "C1005X7S1A474K050BC")
      (footprint "CAP-0402")
      (description "CAP CER 0.47UF 10V X7S 0402")
      (fields
        (field (name "MANUFACTURER") "TDK Corporation")
        (field (name "TOLERANCE") "±10%")
        (field (name "CAPACITANCE") "0.47µF")
      )
      (libsource (lib "zynq_dev_V1") (part "C1005X7S1A474K050BC"))
    )
    (comp (ref "C157")
      (value "C1005X7S1A474K050BC")
      (footprint "CAP-0402")
      (description "CAP CER 0.47UF 10V X7S 0402")
      (fields
        (field (name "MANUFACTURER") "TDK Corporation")
        (field (name "TOLERANCE") "±10%")
        (field (name "CAPACITANCE") "0.47µF")
      )
      (libsource (lib "zynq_dev_V1") (part "C1005X7S1A474K050BC"))
    )
    (comp (ref "C158")
      (value "C1005X7S1A474K050BC")
      (footprint "CAP-0402")
      (description "CAP CER 0.47UF 10V X7S 0402")
      (fields
        (field (name "MANUFACTURER") "TDK Corporation")
        (field (name "TOLERANCE") "±10%")
        (field (name "CAPACITANCE") "0.47µF")
      )
      (libsource (lib "zynq_dev_V1") (part "C1005X7S1A474K050BC"))
    )
    (comp (ref "C159")
      (value "C1005X7S1A474K050BC")
      (footprint "CAP-0402")
      (description "CAP CER 0.47UF 10V X7S 0402")
      (fields
        (field (name "MANUFACTURER") "TDK Corporation")
        (field (name "TOLERANCE") "±10%")
        (field (name "CAPACITANCE") "0.47µF")
      )
      (libsource (lib "zynq_dev_V1") (part "C1005X7S1A474K050BC"))
    )
    (comp (ref "C160")
      (value "C1005X7S1A474K050BC")
      (footprint "CAP-0402")
      (description "CAP CER 0.47UF 10V X7S 0402")
      (fields
        (field (name "MANUFACTURER") "TDK Corporation")
        (field (name "TOLERANCE") "±10%")
        (field (name "CAPACITANCE") "0.47µF")
      )
      (libsource (lib "zynq_dev_V1") (part "C1005X7S1A474K050BC"))
    )
    (comp (ref "C161")
      (value "C1005X7S1A474K050BC")
      (footprint "CAP-0402")
      (description "CAP CER 0.47UF 10V X7S 0402")
      (fields
        (field (name "MANUFACTURER") "TDK Corporation")
        (field (name "TOLERANCE") "±10%")
        (field (name "CAPACITANCE") "0.47µF")
      )
      (libsource (lib "zynq_dev_V1") (part "C1005X7S1A474K050BC"))
    )
    (comp (ref "P1")
      (value "0878311420")
      (footprint "87831-1420")
      (description "CONN HEADER 14POS 2MM VERT GOLD")
      (fields (field (name "MANUFACTURER") "Molex, LLC"))
      (libsource (lib "zynq_dev_V1") (part "0878311420"))
    )
    (comp (ref "R31")
      (value "ERJ-3EKF4701V")
      (footprint "R0603")
      (description "RES SMD 4.7K OHM 1% 1/10W 0603")
      (fields
        (field (name "MANUFACTURER") "Panasonic Electronic Components")
        (field (name "TOLERANCE") "±1%")
        (field (name "RESISTANCE (OHMS)") "4.7k")
      )
      (libsource (lib "zynq_dev_V1") (part "ERJ-3EKF4701V"))
    )
    (comp (ref "R32")
      (value "ERJ-3EKF4701V")
      (footprint "R0603")
      (description "RES SMD 4.7K OHM 1% 1/10W 0603")
      (fields
        (field (name "MANUFACTURER") "Panasonic Electronic Components")
        (field (name "TOLERANCE") "±1%")
        (field (name "RESISTANCE (OHMS)") "4.7k")
      )
      (libsource (lib "zynq_dev_V1") (part "ERJ-3EKF4701V"))
    )
    (comp (ref "R33")
      (value "ERJ-3EKF4701V")
      (footprint "R0603")
      (description "RES SMD 4.7K OHM 1% 1/10W 0603")
      (fields
        (field (name "MANUFACTURER") "Panasonic Electronic Components")
        (field (name "TOLERANCE") "±1%")
        (field (name "RESISTANCE (OHMS)") "4.7k")
      )
      (libsource (lib "zynq_dev_V1") (part "ERJ-3EKF4701V"))
    )
    (comp (ref "R34")
      (value "ERJ-3EKF4701V")
      (footprint "R0603")
      (description "RES SMD 4.7K OHM 1% 1/10W 0603")
      (fields
        (field (name "MANUFACTURER") "Panasonic Electronic Components")
        (field (name "TOLERANCE") "±1%")
        (field (name "RESISTANCE (OHMS)") "4.7k")
      )
      (libsource (lib "zynq_dev_V1") (part "ERJ-3EKF4701V"))
    )
    (comp (ref "R35")
      (value "RC0603FR-07100RL")
      (footprint "R0603")
      (description "RES SMD 100 OHM 1% 1/10W 0603")
      (fields
        (field (name "MANUFACTURER") "Yageo")
        (field (name "TOLERANCE") "±1%")
        (field (name "RESISTANCE (OHMS)") "100")
      )
      (libsource (lib "zynq_dev_V1") (part "RC0603FR-07100RL"))
    )
    (comp (ref "R36")
      (value "RC0603FR-07100RL")
      (footprint "R0603")
      (description "RES SMD 100 OHM 1% 1/10W 0603")
      (fields
        (field (name "MANUFACTURER") "Yageo")
        (field (name "TOLERANCE") "±1%")
        (field (name "RESISTANCE (OHMS)") "100")
      )
      (libsource (lib "zynq_dev_V1") (part "RC0603FR-07100RL"))
    )
    (comp (ref "R37")
      (value "RC0603FR-07100RL")
      (footprint "R0603")
      (description "RES SMD 100 OHM 1% 1/10W 0603")
      (fields
        (field (name "MANUFACTURER") "Yageo")
        (field (name "TOLERANCE") "±1%")
        (field (name "RESISTANCE (OHMS)") "100")
      )
      (libsource (lib "zynq_dev_V1") (part "RC0603FR-07100RL"))
    )
    (comp (ref "R38")
      (value "RC0603FR-07100RL")
      (footprint "R0603")
      (description "RES SMD 100 OHM 1% 1/10W 0603")
      (fields
        (field (name "MANUFACTURER") "Yageo")
        (field (name "TOLERANCE") "±1%")
        (field (name "RESISTANCE (OHMS)") "100")
      )
      (libsource (lib "zynq_dev_V1") (part "RC0603FR-07100RL"))
    )
    (comp (ref "R39")
      (value "ERJ-3EKF4701V")
      (footprint "R0603")
      (description "RES SMD 4.7K OHM 1% 1/10W 0603")
      (fields
        (field (name "MANUFACTURER") "Panasonic Electronic Components")
        (field (name "TOLERANCE") "±1%")
        (field (name "RESISTANCE (OHMS)") "4.7k")
      )
      (libsource (lib "zynq_dev_V1") (part "ERJ-3EKF4701V"))
    )
    (comp (ref "R40")
      (value "RC0603FR-0710KL")
      (footprint "R0603")
      (description "RES SMD 10K OHM 1% 1/10W 0603")
      (fields
        (field (name "MANUFACTURER") "Yageo")
        (field (name "TOLERANCE") "±1%")
        (field (name "RESISTANCE (OHMS)") "10k")
      )
      (libsource (lib "zynq_dev_V1") (part "RC0603FR-0710KL"))
    )
    (comp (ref "R41")
      (value "ERJ-3GEY0R00V")
      (footprint "R0603")
      (description "RES SMD 0.0OHM JUMPER 1/10W 0603")
      (fields
        (field (name "MANUFACTURER") "Panasonic Electronic Components")
        (field (name "TOLERANCE") "Jumper")
        (field (name "RESISTANCE (OHMS)") "0.0")
      )
      (libsource (lib "zynq_dev_V1") (part "ERJ-3GEY0R00V"))
    )
    (comp (ref "R42")
      (value "RC0603FR-0710KL")
      (footprint "R0603")
      (description "RES SMD 10K OHM 1% 1/10W 0603")
      (fields
        (field (name "MANUFACTURER") "Yageo")
        (field (name "TOLERANCE") "±1%")
        (field (name "RESISTANCE (OHMS)") "10k")
      )
      (libsource (lib "zynq_dev_V1") (part "RC0603FR-0710KL"))
    )
    (comp (ref "R43")
      (value "RC0603FR-0710KL")
      (footprint "R0603")
      (description "RES SMD 10K OHM 1% 1/10W 0603")
      (fields
        (field (name "MANUFACTURER") "Yageo")
        (field (name "TOLERANCE") "±1%")
        (field (name "RESISTANCE (OHMS)") "10k")
      )
      (libsource (lib "zynq_dev_V1") (part "RC0603FR-0710KL"))
    )
    (comp (ref "R44")
      (value "ERJ-3GEY0R00V")
      (footprint "R0603")
      (description "RES SMD 0.0OHM JUMPER 1/10W 0603")
      (fields
        (field (name "MANUFACTURER") "Panasonic Electronic Components")
        (field (name "TOLERANCE") "Jumper")
        (field (name "RESISTANCE (OHMS)") "0.0")
      )
      (libsource (lib "zynq_dev_V1") (part "ERJ-3GEY0R00V"))
    )
    (comp (ref "U1")
      (value "XC7Z020-1CLG484I")
      (footprint "CLG484")
      (description "IC SOC CORTEX-A9 ARTIX-7 484BGA")
      (fields (field (name "MANUFACTURER") "Xilinx Inc."))
      (libsource (lib "") (part "XC7Z020-1CLG484I_1"))
    )
  )
  (nets
    (net (code "1") (name "/PL_DONE") (class "Default")
      (node (ref "U1") (pin "T12") (pinfunction "DONE_0_T12") (pintype "bidirectional"))
    )
    (net (code "2") (name "/PROG") (class "Default")
      (node (ref "U1") (pin "T11") (pinfunction "PROGRAM_B_0_T11") (pintype "input"))
    )
    (net (code "3") (name "/PROG-RST") (class "Default")
      (node (ref "P1") (pin "14") (pinfunction "14_14") (pintype "passive"))
    )
    (net (code "4") (name "/TCK") (class "Default")
      (node (ref "R34") (pin "1") (pinfunction "1_1") (pintype "passive"))
      (node (ref "R37") (pin "1") (pinfunction "1_1") (pintype "passive"))
      (node (ref "U1") (pin "G11") (pinfunction "TCK_0_G11") (pintype "input"))
    )
    (net (code "5") (name "/TCK-JTAG") (class "Default")
      (node (ref "P1") (pin "6") (pinfunction "6_6") (pintype "passive"))
      (node (ref "R37") (pin "2") (pinfunction "2_2") (pintype "passive"))
    )
    (net (code "6") (name "/TDI") (class "Default")
      (node (ref "R33") (pin "1") (pinfunction "1_1") (pintype "passive"))
      (node (ref "R35") (pin "1") (pinfunction "1_1") (pintype "passive"))
      (node (ref "U1") (pin "H13") (pinfunction "TDI_0_H13") (pintype "input"))
    )
    (net (code "7") (name "/TDI-JTAG") (class "Default")
      (node (ref "P1") (pin "10") (pinfunction "10_10") (pintype "passive"))
      (node (ref "R35") (pin "2") (pinfunction "2_2") (pintype "passive"))
    )
    (net (code "8") (name "/TDO") (class "Default")
      (node (ref "R31") (pin "1") (pinfunction "1_1") (pintype "passive"))
      (node (ref "R36") (pin "1") (pinfunction "1_1") (pintype "passive"))
      (node (ref "U1") (pin "G14") (pinfunction "TDO_0_G14") (pintype "output"))
    )
    (net (code "9") (name "/TDO-JTAG") (class "Default")
      (node (ref "P1") (pin "8") (pinfunction "8_8") (pintype "passive"))
      (node (ref "R36") (pin "2") (pinfunction "2_2") (pintype "passive"))
    )
    (net (code "10") (name "/TMS") (class "Default")
      (node (ref "R32") (pin "1") (pinfunction "1_1") (pintype "passive"))
      (node (ref "R38") (pin "1") (pinfunction "1_1") (pintype "passive"))
      (node (ref "U1") (pin "G12") (pinfunction "TMS_0_G12") (pintype "input"))
    )
    (net (code "11") (name "/TMS-JTAG") (class "Default")
      (node (ref "P1") (pin "4") (pinfunction "4_4") (pintype "passive"))
      (node (ref "R38") (pin "2") (pinfunction "2_2") (pintype "passive"))
    )
    (net (code "12") (name "/VCCADC_0") (class "Default")
      (node (ref "U1") (pin "K11") (pinfunction "VCCADC_0_K11") (pintype "power_in"))
    )
    (net (code "13") (name "/XADC-AGND") (class "Default")
      (node (ref "R44") (pin "2") (pinfunction "2_2") (pintype "passive"))
      (node (ref "U1") (pin "K12") (pinfunction "GNDADC_0_K12") (pintype "power_in"))
      (node (ref "U1") (pin "L12") (pinfunction "VREFN_0_L12") (pintype "input"))
      (node (ref "U1") (pin "M11") (pinfunction "VREFP_0_M11") (pintype "input"))
    )
    (net (code "14") (name "DDR1V5") (class "Default")
      (node (ref "U1") (pin "E2") (pinfunction "VCCO_DDR_502_E2") (pintype "power_in"))
      (node (ref "U1") (pin "F5") (pinfunction "VCCO_DDR_502_F5") (pintype "power_in"))
      (node (ref "U1") (pin "H1") (pinfunction "VCCO_DDR_502_H1") (pintype "power_in"))
      (node (ref "U1") (pin "J4") (pinfunction "VCCO_DDR_502_J4") (pintype "power_in"))
      (node (ref "U1") (pin "K7") (pinfunction "VCCO_DDR_502_K7") (pintype "power_in"))
      (node (ref "U1") (pin "M3") (pinfunction "VCCO_DDR_502_M3") (pintype "power_in"))
      (node (ref "U1") (pin "N6") (pinfunction "VCCO_DDR_502_N6") (pintype "power_in"))
      (node (ref "U1") (pin "R2") (pinfunction "VCCO_DDR_502_R2") (pintype "power_in"))
      (node (ref "U1") (pin "V1") (pinfunction "VCCO_DDR_502_V1") (pintype "power_in"))
    )
    (net (code "15") (name "GND") (class "Default")
      (node (ref "C100") (pin "2") (pinfunction "2_2") (pintype "passive"))
      (node (ref "C101") (pin "2") (pinfunction "2_2") (pintype "passive"))
      (node (ref "C102") (pin "2") (pinfunction "2_2") (pintype "passive"))
      (node (ref "C103") (pin "2") (pinfunction "2_2") (pintype "passive"))
      (node (ref "C104") (pin "2") (pinfunction "2_2") (pintype "passive"))
      (node (ref "C105") (pin "2") (pinfunction "2_2") (pintype "passive"))
      (node (ref "C106") (pin "2") (pinfunction "2_2") (pintype "passive"))
      (node (ref "C107") (pin "2") (pinfunction "2_2") (pintype "passive"))
      (node (ref "C108") (pin "2") (pinfunction "2_2") (pintype "passive"))
      (node (ref "C109") (pin "2") (pinfunction "2_2") (pintype "passive"))
      (node (ref "C110") (pin "2") (pinfunction "2_2") (pintype "passive"))
      (node (ref "C111") (pin "2") (pinfunction "2_2") (pintype "passive"))
      (node (ref "C112") (pin "2") (pinfunction "2_2") (pintype "passive"))
      (node (ref "C113") (pin "2") (pinfunction "2_2") (pintype "passive"))
      (node (ref "C114") (pin "2") (pinfunction "2_2") (pintype "passive"))
      (node (ref "C115") (pin "2") (pinfunction "2_2") (pintype "passive"))
      (node (ref "C116") (pin "2") (pinfunction "2_2") (pintype "passive"))
      (node (ref "C117") (pin "2") (pinfunction "2_2") (pintype "passive"))
      (node (ref "C118") (pin "2") (pinfunction "2_2") (pintype "passive"))
      (node (ref "C119") (pin "2") (pinfunction "2_2") (pintype "passive"))
      (node (ref "C120") (pin "2") (pinfunction "2_2") (pintype "passive"))
      (node (ref "C121") (pin "2") (pinfunction "2_2") (pintype "passive"))
      (node (ref "C122") (pin "2") (pinfunction "2_2") (pintype "passive"))
      (node (ref "C123") (pin "2") (pinfunction "2_2") (pintype "passive"))
      (node (ref "C124") (pin "2") (pinfunction "2_2") (pintype "passive"))
      (node (ref "C125") (pin "2") (pinfunction "2_2") (pintype "passive"))
      (node (ref "C126") (pin "2") (pinfunction "2_2") (pintype "passive"))
      (node (ref "C127") (pin "2") (pinfunction "2_2") (pintype "passive"))
      (node (ref "C128") (pin "2") (pinfunction "2_2") (pintype "passive"))
      (node (ref "C129") (pin "2") (pinfunction "2_2") (pintype "passive"))
      (node (ref "C130") (pin "2") (pinfunction "2_2") (pintype "passive"))
      (node (ref "C131") (pin "2") (pinfunction "2_2") (pintype "passive"))
      (node (ref "C132") (pin "2") (pinfunction "2_2") (pintype "passive"))
      (node (ref "C133") (pin "2") (pinfunction "2_2") (pintype "passive"))
      (node (ref "C134") (pin "2") (pinfunction "2_2") (pintype "passive"))
      (node (ref "C135") (pin "2") (pinfunction "2_2") (pintype "passive"))
      (node (ref "C136") (pin "2") (pinfunction "2_2") (pintype "passive"))
      (node (ref "C137") (pin "2") (pinfunction "2_2") (pintype "passive"))
      (node (ref "C138") (pin "2") (pinfunction "2_2") (pintype "passive"))
      (node (ref "C139") (pin "2") (pinfunction "2_2") (pintype "passive"))
      (node (ref "C140") (pin "2") (pinfunction "2_2") (pintype "passive"))
      (node (ref "C141") (pin "2") (pinfunction "2_2") (pintype "passive"))
      (node (ref "C142") (pin "2") (pinfunction "2_2") (pintype "passive"))
      (node (ref "C143") (pin "2") (pinfunction "2_2") (pintype "passive"))
      (node (ref "C144") (pin "2") (pinfunction "2_2") (pintype "passive"))
      (node (ref "C145") (pin "2") (pinfunction "2_2") (pintype "passive"))
      (node (ref "C146") (pin "2") (pinfunction "2_2") (pintype "passive"))
      (node (ref "C147") (pin "2") (pinfunction "2_2") (pintype "passive"))
      (node (ref "C148") (pin "2") (pinfunction "2_2") (pintype "passive"))
      (node (ref "C149") (pin "2") (pinfunction "2_2") (pintype "passive"))
      (node (ref "C150") (pin "2") (pinfunction "2_2") (pintype "passive"))
      (node (ref "C151") (pin "2") (pinfunction "2_2") (pintype "passive"))
      (node (ref "C152") (pin "2") (pinfunction "2_2") (pintype "passive"))
      (node (ref "C153") (pin "2") (pinfunction "2_2") (pintype "passive"))
      (node (ref "C154") (pin "2") (pinfunction "2_2") (pintype "passive"))
      (node (ref "C155") (pin "2") (pinfunction "2_2") (pintype "passive"))
      (node (ref "C156") (pin "2") (pinfunction "2_2") (pintype "passive"))
      (node (ref "C157") (pin "2") (pinfunction "2_2") (pintype "passive"))
      (node (ref "C158") (pin "2") (pinfunction "2_2") (pintype "passive"))
      (node (ref "C159") (pin "2") (pinfunction "2_2") (pintype "passive"))
      (node (ref "C160") (pin "2") (pinfunction "2_2") (pintype "passive"))
      (node (ref "C161") (pin "2") (pinfunction "2_2") (pintype "passive"))
      (node (ref "C56") (pin "2") (pinfunction "2_2") (pintype "passive"))
      (node (ref "C57") (pin "2") (pinfunction "2_2") (pintype "passive"))
      (node (ref "C58") (pin "2") (pinfunction "2_2") (pintype "passive"))
      (node (ref "C59") (pin "2") (pinfunction "2_2") (pintype "passive"))
      (node (ref "C60") (pin "2") (pinfunction "2_2") (pintype "passive"))
      (node (ref "C61") (pin "2") (pinfunction "2_2") (pintype "passive"))
      (node (ref "C62") (pin "2") (pinfunction "2_2") (pintype "passive"))
      (node (ref "C63") (pin "2") (pinfunction "2_2") (pintype "passive"))
      (node (ref "C64") (pin "2") (pinfunction "2_2") (pintype "passive"))
      (node (ref "C65") (pin "2") (pinfunction "2_2") (pintype "passive"))
      (node (ref "C66") (pin "2") (pinfunction "2_2") (pintype "passive"))
      (node (ref "C67") (pin "2") (pinfunction "2_2") (pintype "passive"))
      (node (ref "C68") (pin "2") (pinfunction "2_2") (pintype "passive"))
      (node (ref "C69") (pin "2") (pinfunction "2_2") (pintype "passive"))
      (node (ref "C70") (pin "2") (pinfunction "2_2") (pintype "passive"))
      (node (ref "C71") (pin "2") (pinfunction "2_2") (pintype "passive"))
      (node (ref "C72") (pin "2") (pinfunction "2_2") (pintype "passive"))
      (node (ref "C73") (pin "2") (pinfunction "2_2") (pintype "passive"))
      (node (ref "C74") (pin "2") (pinfunction "2_2") (pintype "passive"))
      (node (ref "C75") (pin "2") (pinfunction "2_2") (pintype "passive"))
      (node (ref "C76") (pin "2") (pinfunction "2_2") (pintype "passive"))
      (node (ref "C77") (pin "2") (pinfunction "2_2") (pintype "passive"))
      (node (ref "C78") (pin "2") (pinfunction "2_2") (pintype "passive"))
      (node (ref "C79") (pin "2") (pinfunction "2_2") (pintype "passive"))
      (node (ref "C80") (pin "2") (pinfunction "2_2") (pintype "passive"))
      (node (ref "C81") (pin "2") (pinfunction "2_2") (pintype "passive"))
      (node (ref "C82") (pin "2") (pinfunction "2_2") (pintype "passive"))
      (node (ref "C83") (pin "2") (pinfunction "2_2") (pintype "passive"))
      (node (ref "C84") (pin "2") (pinfunction "2_2") (pintype "passive"))
      (node (ref "C85") (pin "2") (pinfunction "2_2") (pintype "passive"))
      (node (ref "C86") (pin "2") (pinfunction "2_2") (pintype "passive"))
      (node (ref "C87") (pin "2") (pinfunction "2_2") (pintype "passive"))
      (node (ref "C88") (pin "2") (pinfunction "2_2") (pintype "passive"))
      (node (ref "C89") (pin "2") (pinfunction "2_2") (pintype "passive"))
      (node (ref "C90") (pin "2") (pinfunction "2_2") (pintype "passive"))
      (node (ref "C91") (pin "2") (pinfunction "2_2") (pintype "passive"))
      (node (ref "C92") (pin "2") (pinfunction "2_2") (pintype "passive"))
      (node (ref "C93") (pin "2") (pinfunction "2_2") (pintype "passive"))
      (node (ref "C94") (pin "2") (pinfunction "2_2") (pintype "passive"))
      (node (ref "C95") (pin "2") (pinfunction "2_2") (pintype "passive"))
      (node (ref "C96") (pin "2") (pinfunction "2_2") (pintype "passive"))
      (node (ref "C97") (pin "2") (pinfunction "2_2") (pintype "passive"))
      (node (ref "C98") (pin "2") (pinfunction "2_2") (pintype "passive"))
      (node (ref "C99") (pin "2") (pinfunction "2_2") (pintype "passive"))
      (node (ref "P1") (pin "1") (pinfunction "1_1") (pintype "passive"))
      (node (ref "P1") (pin "11") (pinfunction "11_11") (pintype "passive"))
      (node (ref "P1") (pin "13") (pinfunction "13_13") (pintype "passive"))
      (node (ref "P1") (pin "3") (pinfunction "3_3") (pintype "passive"))
      (node (ref "P1") (pin "5") (pinfunction "5_5") (pintype "passive"))
      (node (ref "P1") (pin "7") (pinfunction "7_7") (pintype "passive"))
      (node (ref "P1") (pin "9") (pinfunction "9_9") (pintype "passive"))
      (node (ref "R41") (pin "2") (pinfunction "2_2") (pintype "passive"))
      (node (ref "R42") (pin "2") (pinfunction "2_2") (pintype "passive"))
      (node (ref "R43") (pin "2") (pinfunction "2_2") (pintype "passive"))
      (node (ref "R44") (pin "1") (pinfunction "1_1") (pintype "passive"))
      (node (ref "U1") (pin "A15") (pinfunction "GND_A15") (pintype "power_in"))
      (node (ref "U1") (pin "A5") (pinfunction "GND_A5") (pintype "power_in"))
      (node (ref "U1") (pin "AA15") (pinfunction "GND_AA15") (pintype "power_in"))
      (node (ref "U1") (pin "AA5") (pinfunction "GND_AA5") (pintype "power_in"))
      (node (ref "U1") (pin "AB18") (pinfunction "GND_AB18") (pintype "power_in"))
      (node (ref "U1") (pin "AB8") (pinfunction "GND_AB8") (pintype "power_in"))
      (node (ref "U1") (pin "B18") (pinfunction "GND_B18") (pintype "power_in"))
      (node (ref "U1") (pin "B8") (pinfunction "GND_B8") (pintype "power_in"))
      (node (ref "U1") (pin "C1") (pinfunction "GND_C1") (pintype "power_in"))
      (node (ref "U1") (pin "C11") (pinfunction "GND_C11") (pintype "power_in"))
      (node (ref "U1") (pin "C21") (pinfunction "GND_C21") (pintype "power_in"))
      (node (ref "U1") (pin "D14") (pinfunction "GND_D14") (pintype "power_in"))
      (node (ref "U1") (pin "D4") (pinfunction "GND_D4") (pintype "power_in"))
      (node (ref "U1") (pin "E17") (pinfunction "GND_E17") (pintype "power_in"))
      (node (ref "U1") (pin "E7") (pinfunction "GND_E7") (pintype "power_in"))
      (node (ref "U1") (pin "F10") (pinfunction "GND_F10") (pintype "power_in"))
      (node (ref "U1") (pin "F20") (pinfunction "GND_F20") (pintype "power_in"))
      (node (ref "U1") (pin "G10") (pinfunction "RSVDGND_G10") (pintype "power_in"))
      (node (ref "U1") (pin "G3") (pinfunction "GND_G3") (pintype "power_in"))
      (node (ref "U1") (pin "H12") (pinfunction "GND_H12") (pintype "power_in"))
      (node (ref "U1") (pin "H14") (pinfunction "GND_H14") (pintype "power_in"))
      (node (ref "U1") (pin "H16") (pinfunction "GND_H16") (pintype "power_in"))
      (node (ref "U1") (pin "H6") (pinfunction "GND_H6") (pintype "power_in"))
      (node (ref "U1") (pin "H8") (pinfunction "GND_H8") (pintype "power_in"))
      (node (ref "U1") (pin "J11") (pinfunction "GND_J11") (pintype "power_in"))
      (node (ref "U1") (pin "J13") (pinfunction "GND_J13") (pintype "power_in"))
      (node (ref "U1") (pin "J19") (pinfunction "GND_J19") (pintype "power_in"))
      (node (ref "U1") (pin "J9") (pinfunction "GND_J9") (pintype "power_in"))
      (node (ref "U1") (pin "K10") (pinfunction "GND_K10") (pintype "power_in"))
      (node (ref "U1") (pin "K14") (pinfunction "GND_K14") (pintype "power_in"))
      (node (ref "U1") (pin "K2") (pinfunction "GND_K2") (pintype "power_in"))
      (node (ref "U1") (pin "K22") (pinfunction "GND_K22") (pintype "power_in"))
      (node (ref "U1") (pin "K8") (pinfunction "GND_K8") (pintype "power_in"))
      (node (ref "U1") (pin "L11") (pinfunction "VP_0_L11") (pintype "input"))
      (node (ref "U1") (pin "L13") (pinfunction "GND_L13") (pintype "power_in"))
      (node (ref "U1") (pin "L15") (pinfunction "GND_L15") (pintype "power_in"))
      (node (ref "U1") (pin "L5") (pinfunction "GND_L5") (pintype "power_in"))
      (node (ref "U1") (pin "L9") (pinfunction "GND_L9") (pintype "power_in"))
      (node (ref "U1") (pin "M10") (pinfunction "GND_M10") (pintype "power_in"))
      (node (ref "U1") (pin "M12") (pinfunction "VN_0_M12") (pintype "input"))
      (node (ref "U1") (pin "M14") (pinfunction "GND_M14") (pintype "power_in"))
      (node (ref "U1") (pin "M18") (pinfunction "GND_M18") (pintype "power_in"))
      (node (ref "U1") (pin "M8") (pinfunction "GND_M8") (pintype "power_in"))
      (node (ref "U1") (pin "N1") (pinfunction "GND_N1") (pintype "power_in"))
      (node (ref "U1") (pin "N13") (pinfunction "GND_N13") (pintype "power_in"))
      (node (ref "U1") (pin "N21") (pinfunction "GND_N21") (pintype "power_in"))
      (node (ref "U1") (pin "N9") (pinfunction "GND_N9") (pintype "power_in"))
      (node (ref "U1") (pin "P10") (pinfunction "GND_P10") (pintype "power_in"))
      (node (ref "U1") (pin "P12") (pinfunction "GND_P12") (pintype "power_in"))
      (node (ref "U1") (pin "P14") (pinfunction "GND_P14") (pintype "power_in"))
      (node (ref "U1") (pin "P4") (pinfunction "GND_P4") (pintype "power_in"))
      (node (ref "U1") (pin "P8") (pinfunction "GND_P8") (pintype "power_in"))
      (node (ref "U1") (pin "R11") (pinfunction "GND_R11") (pintype "power_in"))
      (node (ref "U1") (pin "R13") (pinfunction "GND_R13") (pintype "power_in"))
      (node (ref "U1") (pin "R17") (pinfunction "GND_R17") (pintype "power_in"))
      (node (ref "U1") (pin "R9") (pinfunction "GND_R9") (pintype "power_in"))
      (node (ref "U1") (pin "T20") (pinfunction "GND_T20") (pintype "power_in"))
      (node (ref "U1") (pin "U13") (pinfunction "GND_U13") (pintype "power_in"))
      (node (ref "U1") (pin "U3") (pinfunction "GND_U3") (pintype "power_in"))
      (node (ref "U1") (pin "V16") (pinfunction "GND_V16") (pintype "power_in"))
      (node (ref "U1") (pin "V6") (pinfunction "GND_V6") (pintype "power_in"))
      (node (ref "U1") (pin "W19") (pinfunction "GND_W19") (pintype "power_in"))
      (node (ref "U1") (pin "W9") (pinfunction "GND_W9") (pintype "power_in"))
      (node (ref "U1") (pin "Y12") (pinfunction "GND_Y12") (pintype "power_in"))
      (node (ref "U1") (pin "Y2") (pinfunction "GND_Y2") (pintype "power_in"))
      (node (ref "U1") (pin "Y22") (pinfunction "GND_Y22") (pintype "power_in"))
    )
    (net (code "16") (name "Net-(U1E-CFGBVS_0)") (class "Default")
      (node (ref "R40") (pin "2") (pinfunction "2_2") (pintype "passive"))
      (node (ref "R41") (pin "1") (pinfunction "1_1") (pintype "passive"))
      (node (ref "U1") (pin "T13") (pinfunction "CFGBVS_0_T13") (pintype "input"))
    )
    (net (code "17") (name "Net-(U1E-DXN_0)") (class "Default")
      (node (ref "R43") (pin "1") (pinfunction "1_1") (pintype "passive"))
      (node (ref "U1") (pin "N12") (pinfunction "DXN_0_N12") (pintype "input"))
    )
    (net (code "18") (name "Net-(U1E-DXP_0)") (class "Default")
      (node (ref "R42") (pin "1") (pinfunction "1_1") (pintype "passive"))
      (node (ref "U1") (pin "N11") (pinfunction "DXP_0_N11") (pintype "input"))
    )
    (net (code "19") (name "Net-(U1E-INIT_B_0)") (class "Default")
      (node (ref "R39") (pin "2") (pinfunction "2_2") (pintype "passive"))
      (node (ref "U1") (pin "T14") (pinfunction "INIT_B_0_T14") (pintype "bidirectional"))
    )
    (net (code "20") (name "VCC1V0") (class "Default")
      (node (ref "C149") (pin "1") (pinfunction "1_1") (pintype "passive"))
      (node (ref "C150") (pin "1") (pinfunction "1_1") (pintype "passive"))
      (node (ref "C151") (pin "1") (pinfunction "1_1") (pintype "passive"))
      (node (ref "C152") (pin "1") (pinfunction "1_1") (pintype "passive"))
      (node (ref "C153") (pin "1") (pinfunction "1_1") (pintype "passive"))
      (node (ref "C154") (pin "1") (pinfunction "1_1") (pintype "passive"))
      (node (ref "C155") (pin "1") (pinfunction "1_1") (pintype "passive"))
      (node (ref "C156") (pin "1") (pinfunction "1_1") (pintype "passive"))
      (node (ref "C157") (pin "1") (pinfunction "1_1") (pintype "passive"))
      (node (ref "C158") (pin "1") (pinfunction "1_1") (pintype "passive"))
      (node (ref "C159") (pin "1") (pinfunction "1_1") (pintype "passive"))
      (node (ref "C160") (pin "1") (pinfunction "1_1") (pintype "passive"))
      (node (ref "C161") (pin "1") (pinfunction "1_1") (pintype "passive"))
      (node (ref "C56") (pin "1") (pinfunction "1_1") (pintype "passive"))
      (node (ref "C57") (pin "1") (pinfunction "1_1") (pintype "passive"))
      (node (ref "C58") (pin "1") (pinfunction "1_1") (pintype "passive"))
      (node (ref "C59") (pin "1") (pinfunction "1_1") (pintype "passive"))
      (node (ref "C60") (pin "1") (pinfunction "1_1") (pintype "passive"))
      (node (ref "C61") (pin "1") (pinfunction "1_1") (pintype "passive"))
      (node (ref "C62") (pin "1") (pinfunction "1_1") (pintype "passive"))
      (node (ref "C63") (pin "1") (pinfunction "1_1") (pintype "passive"))
      (node (ref "C64") (pin "1") (pinfunction "1_1") (pintype "passive"))
      (node (ref "C65") (pin "1") (pinfunction "1_1") (pintype "passive"))
      (node (ref "C66") (pin "1") (pinfunction "1_1") (pintype "passive"))
      (node (ref "C67") (pin "1") (pinfunction "1_1") (pintype "passive"))
      (node (ref "C68") (pin "1") (pinfunction "1_1") (pintype "passive"))
      (node (ref "C69") (pin "1") (pinfunction "1_1") (pintype "passive"))
      (node (ref "C70") (pin "1") (pinfunction "1_1") (pintype "passive"))
      (node (ref "C71") (pin "1") (pinfunction "1_1") (pintype "passive"))
      (node (ref "C72") (pin "1") (pinfunction "1_1") (pintype "passive"))
      (node (ref "C73") (pin "1") (pinfunction "1_1") (pintype "passive"))
      (node (ref "C74") (pin "1") (pinfunction "1_1") (pintype "passive"))
      (node (ref "C75") (pin "1") (pinfunction "1_1") (pintype "passive"))
      (node (ref "C76") (pin "1") (pinfunction "1_1") (pintype "passive"))
      (node (ref "C77") (pin "1") (pinfunction "1_1") (pintype "passive"))
      (node (ref "C78") (pin "1") (pinfunction "1_1") (pintype "passive"))
      (node (ref "C79") (pin "1") (pinfunction "1_1") (pintype "passive"))
      (node (ref "C80") (pin "1") (pinfunction "1_1") (pintype "passive"))
      (node (ref "C81") (pin "1") (pinfunction "1_1") (pintype "passive"))
      (node (ref "C82") (pin "1") (pinfunction "1_1") (pintype "passive"))
      (node (ref "C83") (pin "1") (pinfunction "1_1") (pintype "passive"))
      (node (ref "C84") (pin "1") (pinfunction "1_1") (pintype "passive"))
      (node (ref "C85") (pin "1") (pinfunction "1_1") (pintype "passive"))
      (node (ref "U1") (pin "G8") (pinfunction "VCCPINT_G8") (pintype "power_in"))
      (node (ref "U1") (pin "H11") (pinfunction "VCCBRAM_H11") (pintype "power_in"))
      (node (ref "U1") (pin "H9") (pinfunction "VCCPINT_H9") (pintype "power_in"))
      (node (ref "U1") (pin "J10") (pinfunction "VCCBRAM_J10") (pintype "power_in"))
      (node (ref "U1") (pin "J12") (pinfunction "VCCINT_J12") (pintype "power_in"))
      (node (ref "U1") (pin "J14") (pinfunction "VCCINT_J14") (pintype "power_in"))
      (node (ref "U1") (pin "J8") (pinfunction "VCCPINT_J8") (pintype "power_in"))
      (node (ref "U1") (pin "K13") (pinfunction "VCCINT_K13") (pintype "power_in"))
      (node (ref "U1") (pin "L14") (pinfunction "VCCINT_L14") (pintype "power_in"))
      (node (ref "U1") (pin "L8") (pinfunction "VCCPINT_L8") (pintype "power_in"))
      (node (ref "U1") (pin "M13") (pinfunction "VCCINT_M13") (pintype "power_in"))
      (node (ref "U1") (pin "N14") (pinfunction "VCCINT_N14") (pintype "power_in"))
      (node (ref "U1") (pin "N8") (pinfunction "VCCPINT_N8") (pintype "power_in"))
      (node (ref "U1") (pin "P13") (pinfunction "VCCINT_P13") (pintype "power_in"))
      (node (ref "U1") (pin "R14") (pinfunction "VCCINT_R14") (pintype "power_in"))
      (node (ref "U1") (pin "R8") (pinfunction "VCCPINT_R8") (pintype "power_in"))
    )
    (net (code "21") (name "VCC1V8") (class "Default")
      (node (ref "C108") (pin "1") (pinfunction "1_1") (pintype "passive"))
      (node (ref "C109") (pin "1") (pinfunction "1_1") (pintype "passive"))
      (node (ref "C110") (pin "1") (pinfunction "1_1") (pintype "passive"))
      (node (ref "C111") (pin "1") (pinfunction "1_1") (pintype "passive"))
      (node (ref "C112") (pin "1") (pinfunction "1_1") (pintype "passive"))
      (node (ref "C113") (pin "1") (pinfunction "1_1") (pintype "passive"))
      (node (ref "C114") (pin "1") (pinfunction "1_1") (pintype "passive"))
      (node (ref "C115") (pin "1") (pinfunction "1_1") (pintype "passive"))
      (node (ref "C86") (pin "1") (pinfunction "1_1") (pintype "passive"))
      (node (ref "C87") (pin "1") (pinfunction "1_1") (pintype "passive"))
      (node (ref "C88") (pin "1") (pinfunction "1_1") (pintype "passive"))
      (node (ref "C89") (pin "1") (pinfunction "1_1") (pintype "passive"))
      (node (ref "C90") (pin "1") (pinfunction "1_1") (pintype "passive"))
      (node (ref "C91") (pin "1") (pinfunction "1_1") (pintype "passive"))
      (node (ref "C92") (pin "1") (pinfunction "1_1") (pintype "passive"))
      (node (ref "U1") (pin "G9") (pinfunction "VCCBATT_0_G9") (pintype "power_in"))
      (node (ref "U1") (pin "K9") (pinfunction "VCCPAUX_K9") (pintype "power_in"))
      (node (ref "U1") (pin "L10") (pinfunction "VCCAUX_L10") (pintype "power_in"))
      (node (ref "U1") (pin "M9") (pinfunction "VCCPAUX_M9") (pintype "power_in"))
      (node (ref "U1") (pin "N10") (pinfunction "VCCAUX_N10") (pintype "power_in"))
      (node (ref "U1") (pin "P11") (pinfunction "VCCAUX_P11") (pintype "power_in"))
      (node (ref "U1") (pin "P9") (pinfunction "VCCPAUX_P9") (pintype "power_in"))
      (node (ref "U1") (pin "R10") (pinfunction "VCCAUX_R10") (pintype "power_in"))
      (node (ref "U1") (pin "T9") (pinfunction "VCCPAUX_T9") (pintype "power_in"))
    )
    (net (code "22") (name "VCC3V3") (class "Default")
      (node (ref "C100") (pin "1") (pinfunction "1_1") (pintype "passive"))
      (node (ref "C101") (pin "1") (pinfunction "1_1") (pintype "passive"))
      (node (ref "C102") (pin "1") (pinfunction "1_1") (pintype "passive"))
      (node (ref "C103") (pin "1") (pinfunction "1_1") (pintype "passive"))
      (node (ref "C104") (pin "1") (pinfunction "1_1") (pintype "passive"))
      (node (ref "C105") (pin "1") (pinfunction "1_1") (pintype "passive"))
      (node (ref "C106") (pin "1") (pinfunction "1_1") (pintype "passive"))
      (node (ref "C107") (pin "1") (pinfunction "1_1") (pintype "passive"))
      (node (ref "C116") (pin "1") (pinfunction "1_1") (pintype "passive"))
      (node (ref "C117") (pin "1") (pinfunction "1_1") (pintype "passive"))
      (node (ref "C118") (pin "1") (pinfunction "1_1") (pintype "passive"))
      (node (ref "C119") (pin "1") (pinfunction "1_1") (pintype "passive"))
      (node (ref "C120") (pin "1") (pinfunction "1_1") (pintype "passive"))
      (node (ref "C121") (pin "1") (pinfunction "1_1") (pintype "passive"))
      (node (ref "C122") (pin "1") (pinfunction "1_1") (pintype "passive"))
      (node (ref "C123") (pin "1") (pinfunction "1_1") (pintype "passive"))
      (node (ref "C124") (pin "1") (pinfunction "1_1") (pintype "passive"))
      (node (ref "C125") (pin "1") (pinfunction "1_1") (pintype "passive"))
      (node (ref "C126") (pin "1") (pinfunction "1_1") (pintype "passive"))
      (node (ref "C127") (pin "1") (pinfunction "1_1") (pintype "passive"))
      (node (ref "C128") (pin "1") (pinfunction "1_1") (pintype "passive"))
      (node (ref "C129") (pin "1") (pinfunction "1_1") (pintype "passive"))
      (node (ref "C130") (pin "1") (pinfunction "1_1") (pintype "passive"))
      (node (ref "C131") (pin "1") (pinfunction "1_1") (pintype "passive"))
      (node (ref "C132") (pin "1") (pinfunction "1_1") (pintype "passive"))
      (node (ref "C133") (pin "1") (pinfunction "1_1") (pintype "passive"))
      (node (ref "C134") (pin "1") (pinfunction "1_1") (pintype "passive"))
      (node (ref "C135") (pin "1") (pinfunction "1_1") (pintype "passive"))
      (node (ref "C136") (pin "1") (pinfunction "1_1") (pintype "passive"))
      (node (ref "C137") (pin "1") (pinfunction "1_1") (pintype "passive"))
      (node (ref "C138") (pin "1") (pinfunction "1_1") (pintype "passive"))
      (node (ref "C139") (pin "1") (pinfunction "1_1") (pintype "passive"))
      (node (ref "C140") (pin "1") (pinfunction "1_1") (pintype "passive"))
      (node (ref "C141") (pin "1") (pinfunction "1_1") (pintype "passive"))
      (node (ref "C142") (pin "1") (pinfunction "1_1") (pintype "passive"))
      (node (ref "C143") (pin "1") (pinfunction "1_1") (pintype "passive"))
      (node (ref "C144") (pin "1") (pinfunction "1_1") (pintype "passive"))
      (node (ref "C145") (pin "1") (pinfunction "1_1") (pintype "passive"))
      (node (ref "C146") (pin "1") (pinfunction "1_1") (pintype "passive"))
      (node (ref "C147") (pin "1") (pinfunction "1_1") (pintype "passive"))
      (node (ref "C148") (pin "1") (pinfunction "1_1") (pintype "passive"))
      (node (ref "C93") (pin "1") (pinfunction "1_1") (pintype "passive"))
      (node (ref "C94") (pin "1") (pinfunction "1_1") (pintype "passive"))
      (node (ref "C95") (pin "1") (pinfunction "1_1") (pintype "passive"))
      (node (ref "C96") (pin "1") (pinfunction "1_1") (pintype "passive"))
      (node (ref "C97") (pin "1") (pinfunction "1_1") (pintype "passive"))
      (node (ref "C98") (pin "1") (pinfunction "1_1") (pintype "passive"))
      (node (ref "C99") (pin "1") (pinfunction "1_1") (pintype "passive"))
      (node (ref "P1") (pin "2") (pinfunction "2_2") (pintype "passive"))
      (node (ref "R31") (pin "2") (pinfunction "2_2") (pintype "passive"))
      (node (ref "R32") (pin "2") (pinfunction "2_2") (pintype "passive"))
      (node (ref "R33") (pin "2") (pinfunction "2_2") (pintype "passive"))
      (node (ref "R34") (pin "2") (pinfunction "2_2") (pintype "passive"))
      (node (ref "R39") (pin "1") (pinfunction "1_1") (pintype "passive"))
      (node (ref "R40") (pin "1") (pinfunction "1_1") (pintype "passive"))
      (node (ref "U1") (pin "A10") (pinfunction "VCCO_MIO1_501_A10") (pintype "power_in"))
      (node (ref "U1") (pin "A20") (pinfunction "VCCO_35_A20") (pintype "power_in"))
      (node (ref "U1") (pin "AA10") (pinfunction "VCCO_13_AA10") (pintype "power_in"))
      (node (ref "U1") (pin "AA20") (pinfunction "VCCO_33_AA20") (pintype "power_in"))
      (node (ref "U1") (pin "AB13") (pinfunction "VCCO_33_AB13") (pintype "power_in"))
      (node (ref "U1") (pin "AB3") (pinfunction "VCCO_13_AB3") (pintype "power_in"))
      (node (ref "U1") (pin "B13") (pinfunction "VCCO_MIO1_501_B13") (pintype "power_in"))
      (node (ref "U1") (pin "B3") (pinfunction "VCCO_MIO0_500_B3") (pintype "power_in"))
      (node (ref "U1") (pin "C16") (pinfunction "VCCO_35_C16") (pintype "power_in"))
      (node (ref "U1") (pin "C6") (pinfunction "VCCO_MIO0_500_C6") (pintype "power_in"))
      (node (ref "U1") (pin "D19") (pinfunction "VCCO_35_D19") (pintype "power_in"))
      (node (ref "U1") (pin "D9") (pinfunction "VCCO_MIO1_501_D9") (pintype "power_in"))
      (node (ref "U1") (pin "E12") (pinfunction "VCCO_MIO1_501_E12") (pintype "power_in"))
      (node (ref "U1") (pin "E22") (pinfunction "VCCO_35_E22") (pintype "power_in"))
      (node (ref "U1") (pin "F15") (pinfunction "VCCO_35_F15") (pintype "power_in"))
      (node (ref "U1") (pin "G18") (pinfunction "VCCO_35_G18") (pintype "power_in"))
      (node (ref "U1") (pin "H21") (pinfunction "VCCO_35_H21") (pintype "power_in"))
      (node (ref "U1") (pin "K17") (pinfunction "VCCO_34_K17") (pintype "power_in"))
      (node (ref "U1") (pin "L20") (pinfunction "VCCO_34_L20") (pintype "power_in"))
      (node (ref "U1") (pin "N16") (pinfunction "VCCO_34_N16") (pintype "power_in"))
      (node (ref "U1") (pin "P19") (pinfunction "VCCO_34_P19") (pintype "power_in"))
      (node (ref "U1") (pin "R12") (pinfunction "VCCO_0_R12") (pintype "power_in"))
      (node (ref "U1") (pin "R22") (pinfunction "VCCO_34_R22") (pintype "power_in"))
      (node (ref "U1") (pin "T10") (pinfunction "RSVDVCC3_T10") (pintype "power_in"))
      (node (ref "U1") (pin "T15") (pinfunction "VCCO_34_T15") (pintype "power_in"))
      (node (ref "U1") (pin "T5") (pinfunction "VCCO_13_T5") (pintype "power_in"))
      (node (ref "U1") (pin "T7") (pinfunction "RSVDVCC1_T7") (pintype "power_in"))
      (node (ref "U1") (pin "T8") (pinfunction "RSVDVCC2_T8") (pintype "power_in"))
      (node (ref "U1") (pin "U18") (pinfunction "VCCO_33_U18") (pintype "power_in"))
      (node (ref "U1") (pin "U8") (pinfunction "VCCO_13_U8") (pintype "power_in"))
      (node (ref "U1") (pin "V11") (pinfunction "VCCO_13_V11") (pintype "power_in"))
      (node (ref "U1") (pin "V21") (pinfunction "VCCO_33_V21") (pintype "power_in"))
      (node (ref "U1") (pin "W14") (pinfunction "VCCO_33_W14") (pintype "power_in"))
      (node (ref "U1") (pin "W4") (pinfunction "VCCO_13_W4") (pintype "power_in"))
      (node (ref "U1") (pin "Y17") (pinfunction "VCCO_33_Y17") (pintype "power_in"))
      (node (ref "U1") (pin "Y7") (pinfunction "VCCO_13_Y7") (pintype "power_in"))
    )
    (net (code "23") (name "unconnected-(P1-Pad12)") (class "Default")
      (node (ref "P1") (pin "12") (pinfunction "12_12") (pintype "passive"))
    )
    (net (code "24") (name "unconnected-(U1I-VCCPLL-PadH10)") (class "Default")
      (node (ref "U1") (pin "H10") (pinfunction "VCCPLL_H10") (pintype "power_in"))
    )
  )
)
